# 25_USB2_USB3_TypeC_Port.net
KiCad netlist of a schematic drawn in Altium Designer
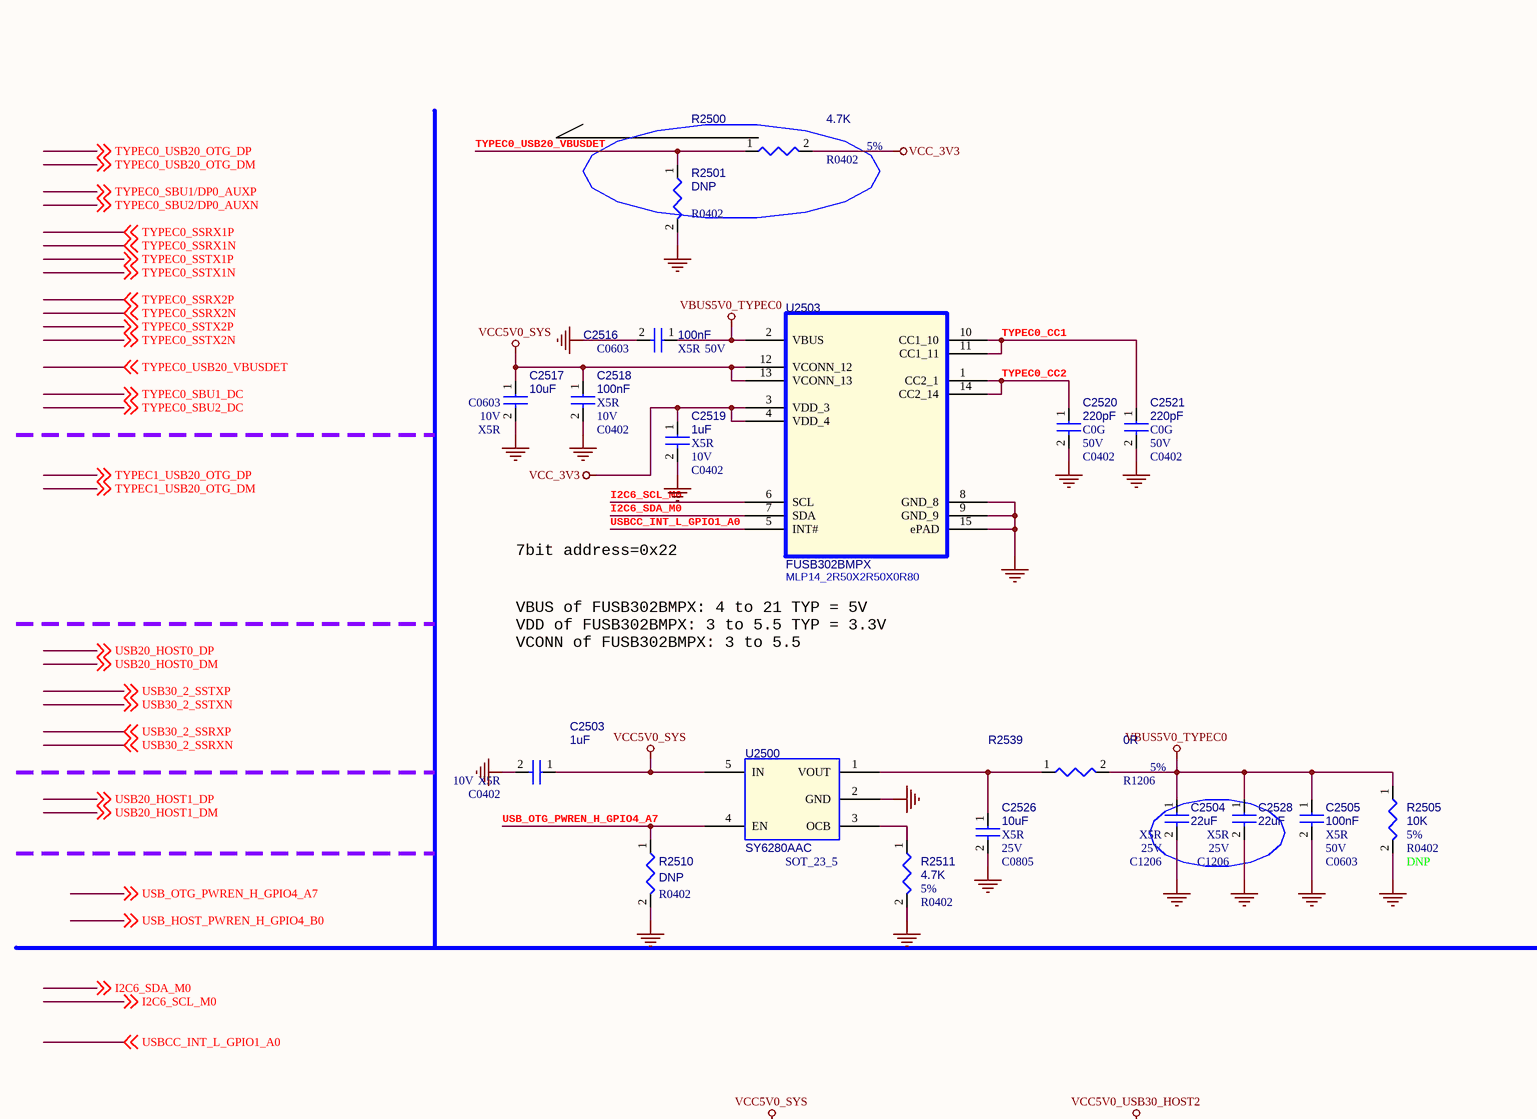
[diagram p0: 25.USB2_USB3_TypeC Port.SchDoc, top left]
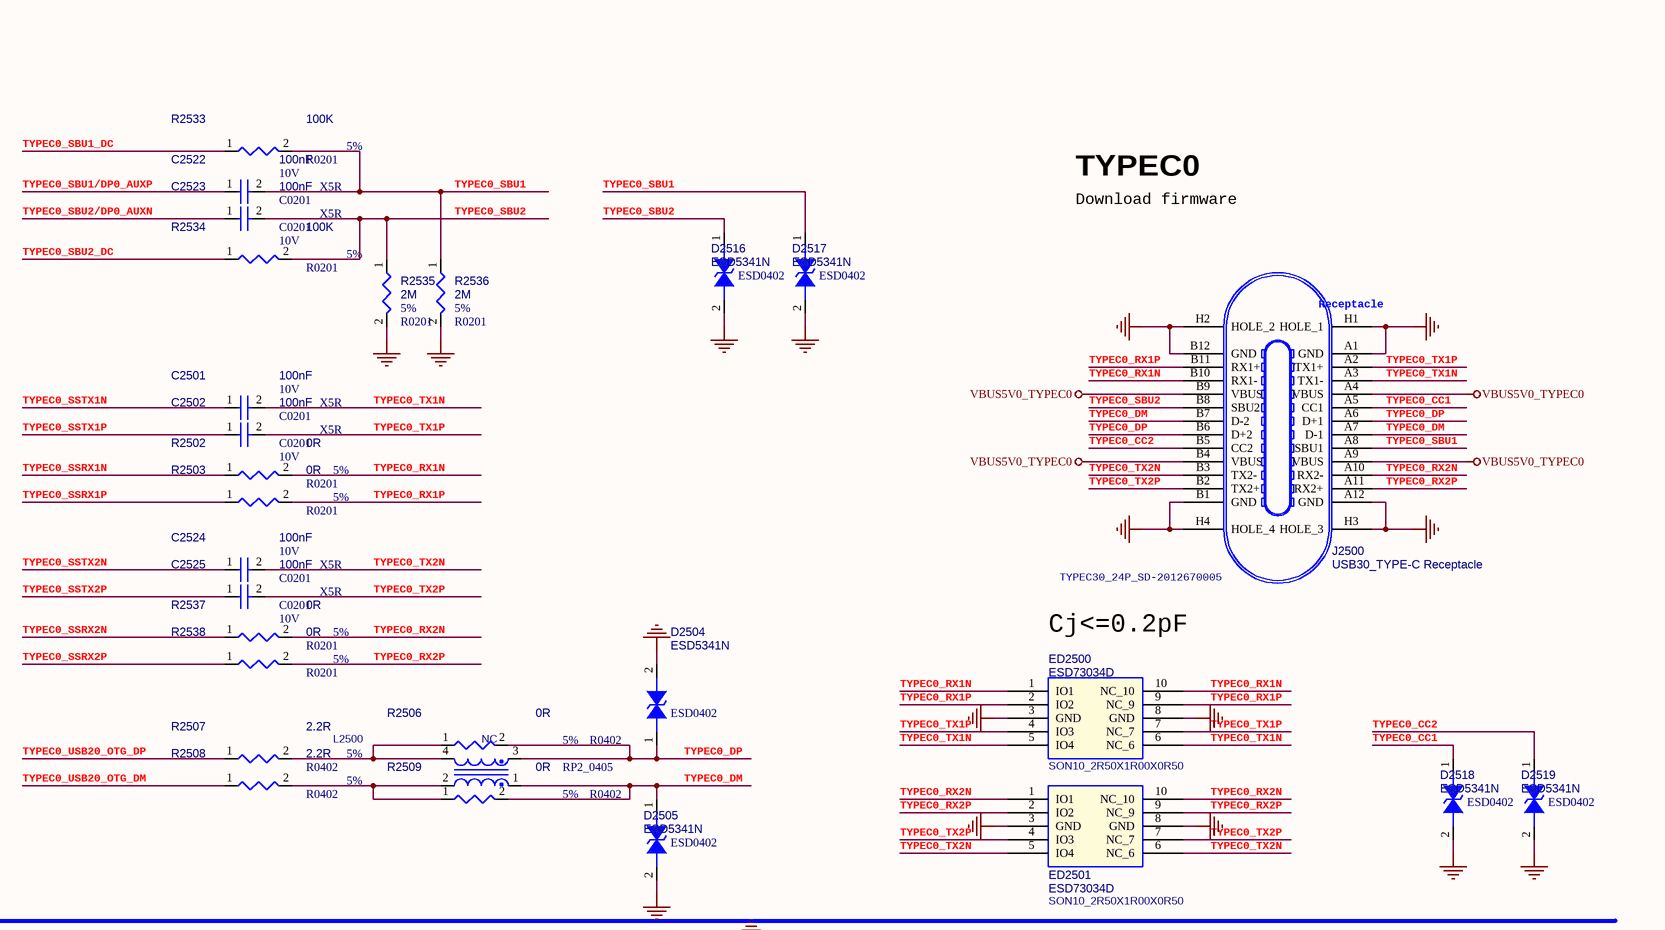
[diagram p1: 25.USB2_USB3_TypeC Port.SchDoc, top right]
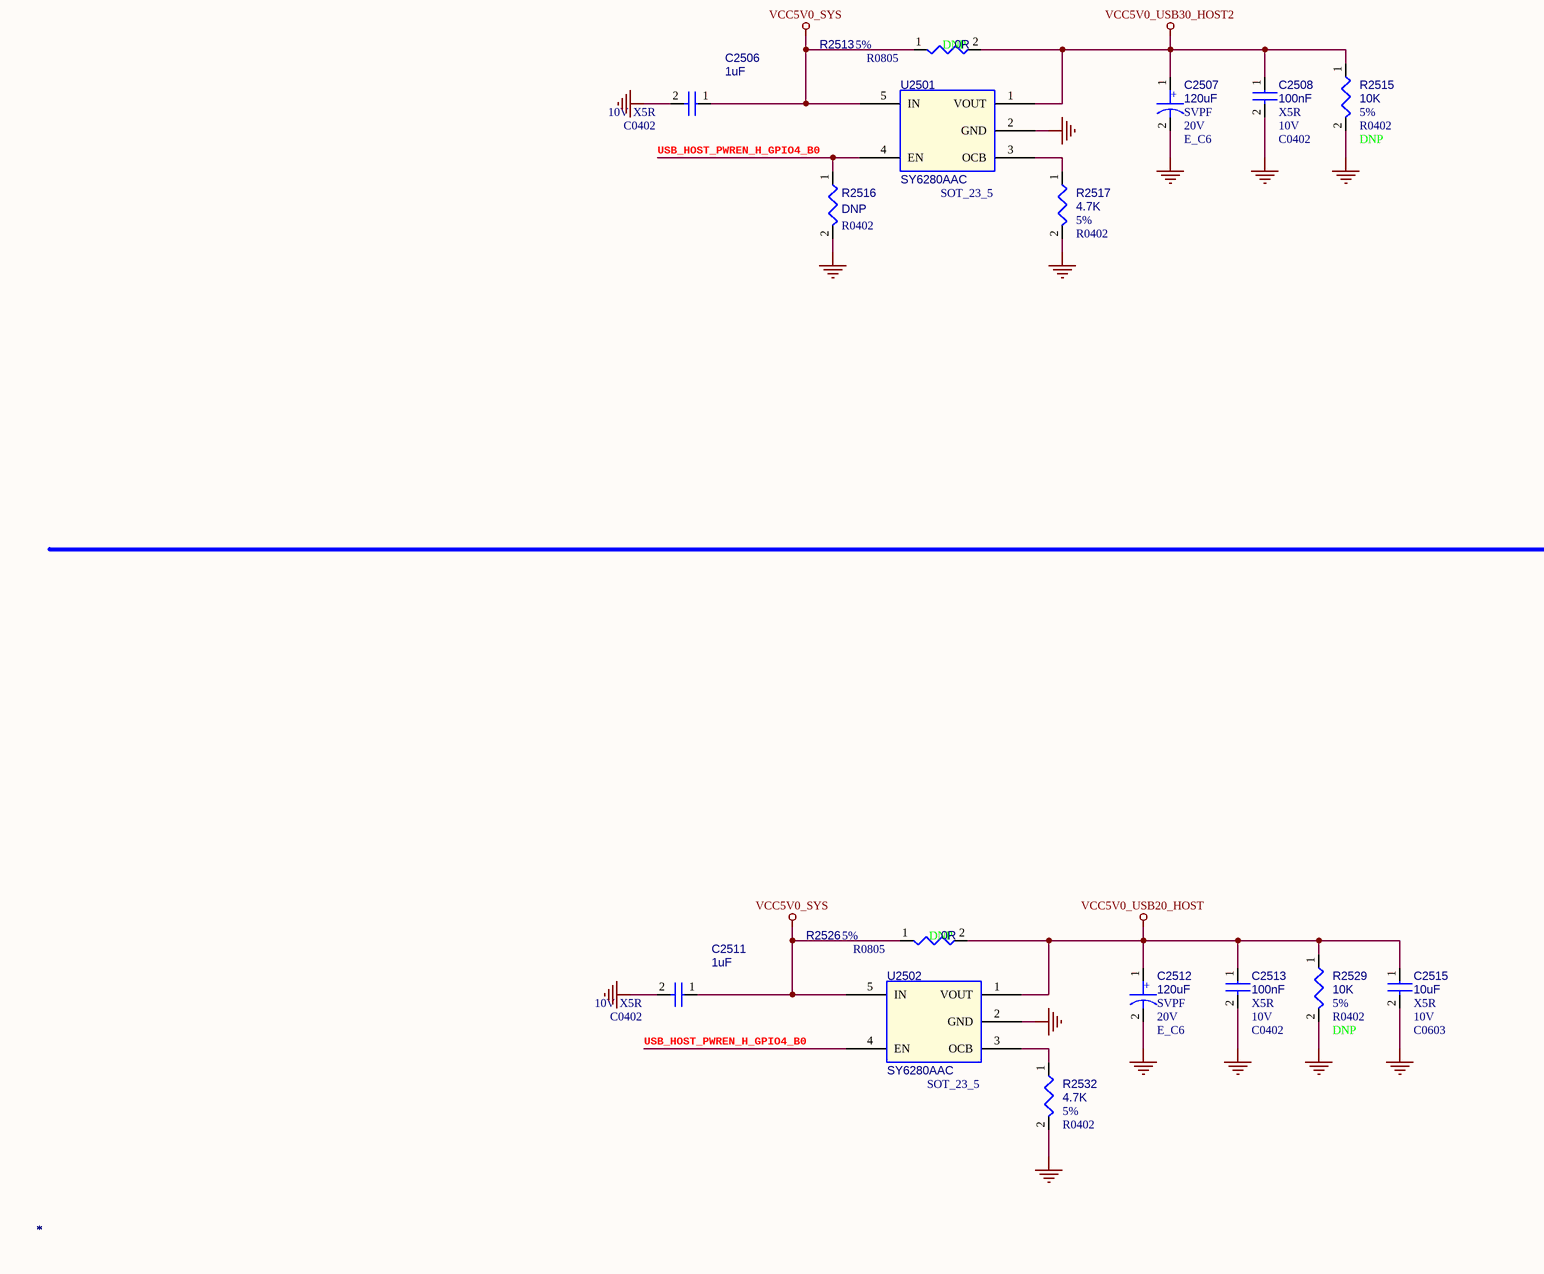
[diagram p2: 25.USB2_USB3_TypeC Port.SchDoc, bottom left]
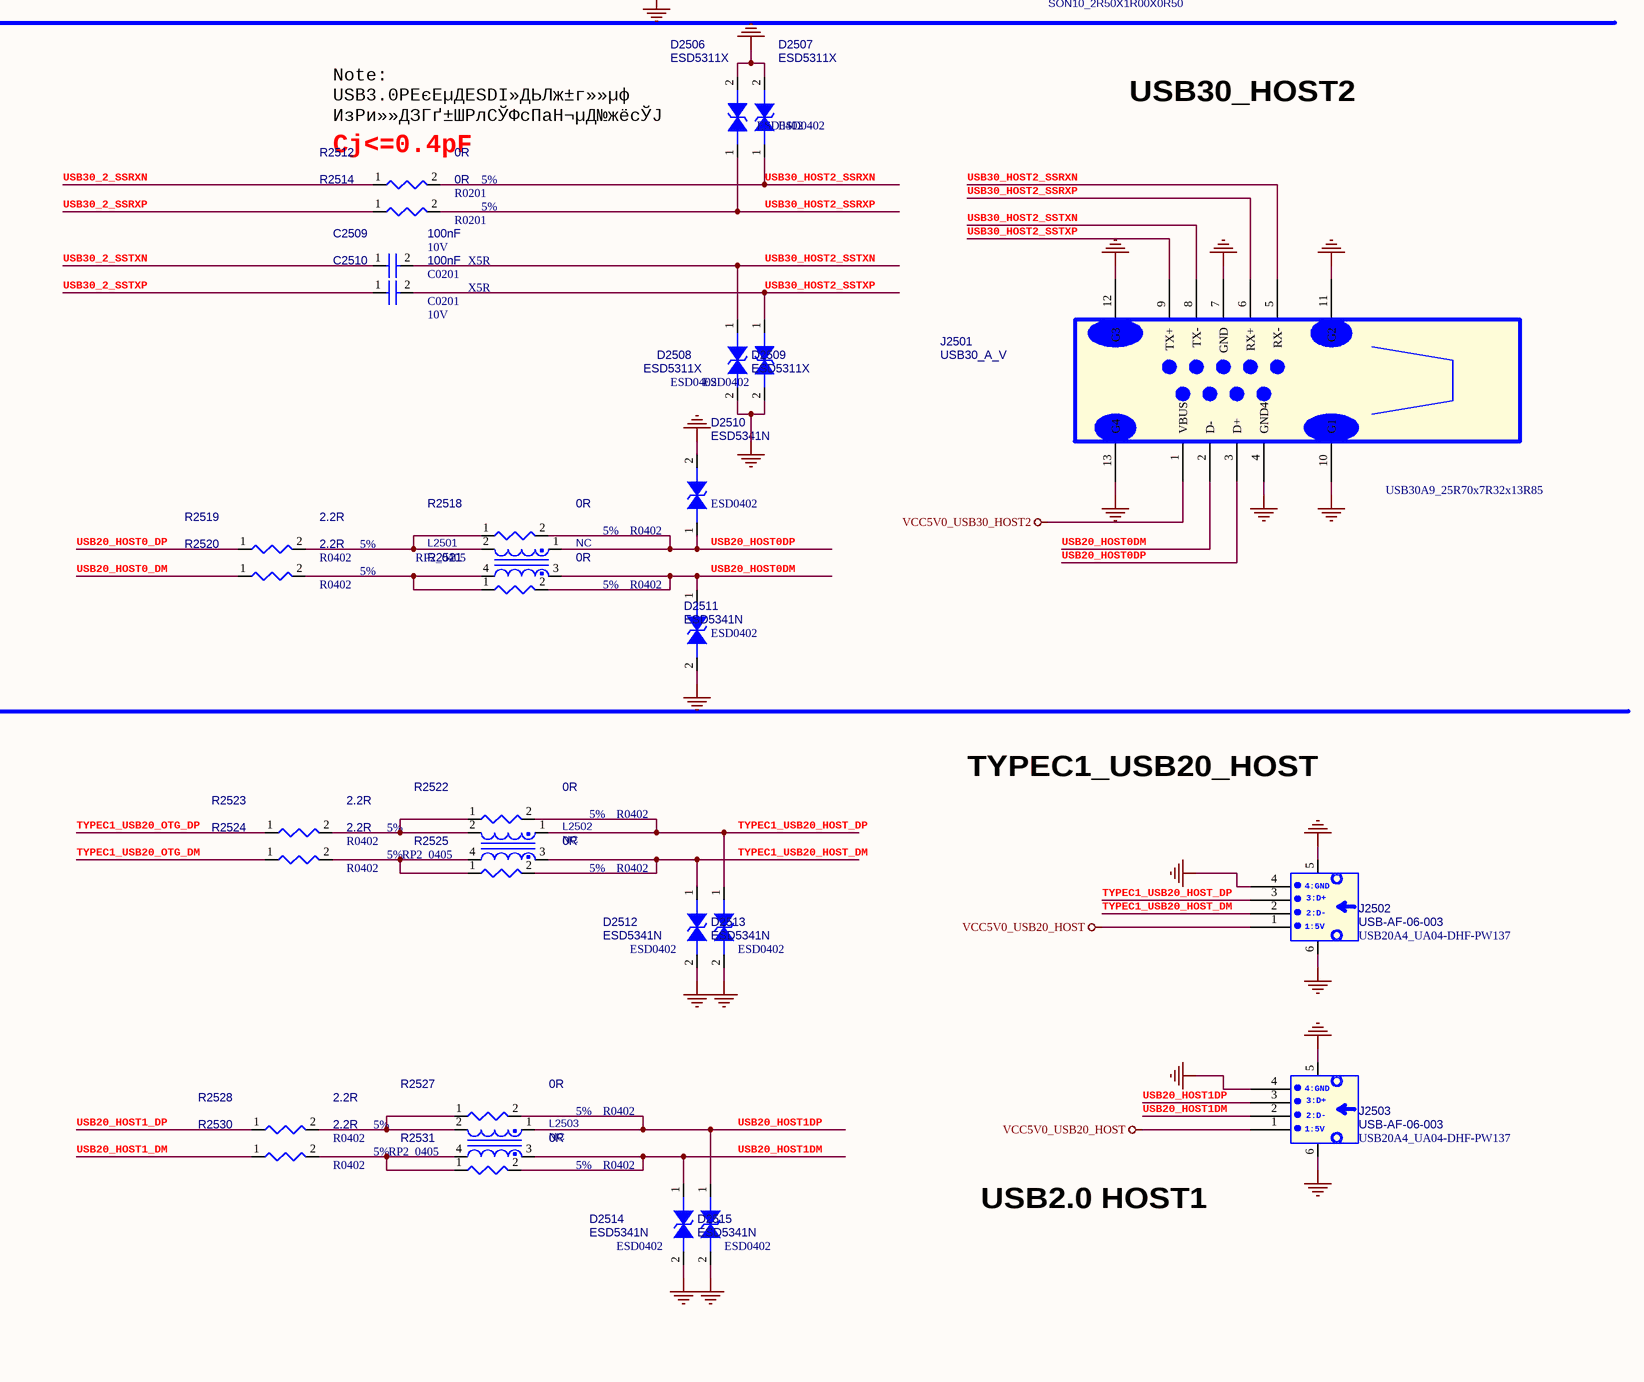
[diagram p3: 25.USB2_USB3_TypeC Port.SchDoc, bottom right]

(export (version "E")
  (design (tool "Eeschema 10.0.6"))
  (components
    (comp (ref "C2501")
      (value "*")
      (footprint "C0201")
      (description "cap,100.00nF,+/-10%,10V,X5R,C0201")
      (fields
        (field (name "VOLTAGE") "10V")
        (field (name "PCB FOOTPRINT") "C0201")
        (field (name "DIELECTRIC") "X5R")
        (field (name "MANUFACTURER") "TDK")
        (field (name "TOLERANCE") "10%")
        (field (name "ALTIUM_UNNAMED_1") "100nF")
        (field (name "CREATED BY") "JJJ")
      )
      (libsource (lib "*") (part "CAP NP"))
    )
    (comp (ref "C2502")
      (value "*")
      (footprint "C0201")
      (description "cap,100.00nF,+/-10%,10V,X5R,C0201")
      (fields
        (field (name "VOLTAGE") "10V")
        (field (name "PCB FOOTPRINT") "C0201")
        (field (name "DIELECTRIC") "X5R")
        (field (name "MANUFACTURER") "TDK")
        (field (name "TOLERANCE") "10%")
        (field (name "ALTIUM_UNNAMED_1") "100nF")
        (field (name "CREATED BY") "JJJ")
      )
      (libsource (lib "*") (part "CAP NP"))
    )
    (comp (ref "C2503")
      (value "*")
      (footprint "C0402")
      (description "cap,1.00uF,+/-10%,10V,X5R,C0402")
      (fields
        (field (name "VOLTAGE") "10V")
        (field (name "PCB FOOTPRINT") "C0402")
        (field (name "DIELECTRIC") "X5R")
        (field (name "MANUFACTURER") "TDK")
        (field (name "TOLERANCE") "10%")
        (field (name "ALTIUM_UNNAMED_1") "1uF")
        (field (name "CREATED BY") "JJJ")
      )
      (libsource (lib "*") (part "CAP NP"))
    )
    (comp (ref "C2504")
      (value "*")
      (footprint "C1206")
      (description "cap,22.00uF,+/-20%,25V,X5R,C1206")
      (fields
        (field (name "VOLTAGE") "25V")
        (field (name "PCB FOOTPRINT") "C1206")
        (field (name "DIELECTRIC") "X5R")
        (field (name "MANUFACTURER") "TDK")
        (field (name "TOLERANCE") "20%")
        (field (name "ALTIUM_UNNAMED_1") "22uF")
        (field (name "CREATED BY") "JJJ")
      )
      (libsource (lib "*") (part "CAP NP"))
    )
    (comp (ref "C2505")
      (value "*")
      (footprint "C0603")
      (description "cap,100.00nF,+/-10%,50V,X5R,C0603")
      (fields
        (field (name "VOLTAGE") "50V")
        (field (name "PCB FOOTPRINT") "C0603")
        (field (name "DIELECTRIC") "X5R")
        (field (name "TOLERANCE") "10%")
        (field (name "MANUFACTURER") "TDK")
        (field (name "ALTIUM_UNNAMED_1") "100nF")
        (field (name "CREATED BY") "JJJ")
      )
      (libsource (lib "*") (part "CAP NP"))
    )
    (comp (ref "C2506")
      (value "*")
      (footprint "C0402")
      (description "cap,1.00uF,+/-10%,10V,X5R,C0402")
      (fields
        (field (name "VOLTAGE") "10V")
        (field (name "PCB FOOTPRINT") "C0402")
        (field (name "DIELECTRIC") "X5R")
        (field (name "MANUFACTURER") "TDK")
        (field (name "TOLERANCE") "10%")
        (field (name "ALTIUM_UNNAMED_1") "1uF")
        (field (name "CREATED BY") "JJJ")
      )
      (libsource (lib "*") (part "CAP NP"))
    )
    (comp (ref "C2507")
      (value "*")
      (footprint "E_C6")
      (description "120uF,20V,25mR,SVPF")
      (fields
        (field (name "VOLTAGE") "20V")
        (field (name "DIELECTRIC") "SVPF")
        (field (name "PCB FOOTPRINT") "E_C6")
        (field (name "TOLERANCE") "20%")
        (field (name "MANUFACTURER") "Panasonic")
        (field (name "ALTIUM_UNNAMED_1") "120uF")
        (field (name "CREATED BY") "YWQ")
      )
      (libsource (lib "*") (part "CAP"))
    )
    (comp (ref "C2508")
      (value "*")
      (footprint "C0402")
      (description "cap,100.00nF,+/-10%,10V,X5R,C0402")
      (fields
        (field (name "VOLTAGE") "10V")
        (field (name "PCB FOOTPRINT") "C0402")
        (field (name "DIELECTRIC") "X5R")
        (field (name "MANUFACTURER") "TDK")
        (field (name "TOLERANCE") "10%")
        (field (name "ALTIUM_UNNAMED_1") "100nF")
        (field (name "CREATED BY") "JJJ")
      )
      (libsource (lib "*") (part "CAP NP"))
    )
    (comp (ref "C2509")
      (value "*")
      (footprint "C0201")
      (description "cap,100.00nF,+/-10%,10V,X5R,C0201")
      (fields
        (field (name "VOLTAGE") "10V")
        (field (name "PCB FOOTPRINT") "C0201")
        (field (name "DIELECTRIC") "X5R")
        (field (name "MANUFACTURER") "TDK")
        (field (name "TOLERANCE") "10%")
        (field (name "ALTIUM_UNNAMED_1") "100nF")
        (field (name "CREATED BY") "JJJ")
      )
      (libsource (lib "*") (part "CAP NP"))
    )
    (comp (ref "C2510")
      (value "*")
      (footprint "C0201")
      (description "cap,100.00nF,+/-10%,10V,X5R,C0201")
      (fields
        (field (name "VOLTAGE") "10V")
        (field (name "PCB FOOTPRINT") "C0201")
        (field (name "DIELECTRIC") "X5R")
        (field (name "MANUFACTURER") "TDK")
        (field (name "TOLERANCE") "10%")
        (field (name "ALTIUM_UNNAMED_1") "100nF")
        (field (name "CREATED BY") "JJJ")
      )
      (libsource (lib "*") (part "CAP NP"))
    )
    (comp (ref "C2511")
      (value "*")
      (footprint "C0402")
      (description "cap,1.00uF,+/-10%,10V,X5R,C0402")
      (fields
        (field (name "VOLTAGE") "10V")
        (field (name "PCB FOOTPRINT") "C0402")
        (field (name "DIELECTRIC") "X5R")
        (field (name "MANUFACTURER") "TDK")
        (field (name "TOLERANCE") "10%")
        (field (name "ALTIUM_UNNAMED_1") "1uF")
        (field (name "CREATED BY") "JJJ")
      )
      (libsource (lib "*") (part "CAP NP"))
    )
    (comp (ref "C2512")
      (value "*")
      (footprint "E_C6")
      (description "120uF,20V,25mR,SVPF")
      (fields
        (field (name "VOLTAGE") "20V")
        (field (name "DIELECTRIC") "SVPF")
        (field (name "PCB FOOTPRINT") "E_C6")
        (field (name "MANUFACTURER") "Panasonic")
        (field (name "TOLERANCE") "20%")
        (field (name "ALTIUM_UNNAMED_1") "120uF")
        (field (name "CREATED BY") "YWQ")
      )
      (libsource (lib "*") (part "CAP"))
    )
    (comp (ref "C2513")
      (value "*")
      (footprint "C0402")
      (description "cap,100.00nF,+/-10%,10V,X5R,C0402")
      (fields
        (field (name "VOLTAGE") "10V")
        (field (name "PCB FOOTPRINT") "C0402")
        (field (name "DIELECTRIC") "X5R")
        (field (name "TOLERANCE") "10%")
        (field (name "MANUFACTURER") "TDK")
        (field (name "ALTIUM_UNNAMED_1") "100nF")
        (field (name "CREATED BY") "JJJ")
      )
      (libsource (lib "*") (part "CAP NP"))
    )
    (comp (ref "C2515")
      (value "*")
      (footprint "C0603")
      (description "cap,10.00uF,+/-10%,10V,X5R,C0603")
      (fields
        (field (name "VOLTAGE") "10V")
        (field (name "PCB FOOTPRINT") "C0603")
        (field (name "DIELECTRIC") "X5R")
        (field (name "MANUFACTURER") "TDK")
        (field (name "TOLERANCE") "10%")
        (field (name "ALTIUM_UNNAMED_1") "10uF")
        (field (name "CREATED BY") "JJJ")
      )
      (libsource (lib "*") (part "CAP NP"))
    )
    (comp (ref "C2516")
      (value "*")
      (footprint "C0603")
      (description "cap,100.00nF,+/-10%,50V,X5R,C0603")
      (fields
        (field (name "VOLTAGE") "50V")
        (field (name "PCB FOOTPRINT") "C0603")
        (field (name "DIELECTRIC") "X5R")
        (field (name "MANUFACTURER") "TDK")
        (field (name "TOLERANCE") "10%")
        (field (name "ALTIUM_UNNAMED_1") "100nF")
        (field (name "CREATED BY") "JJJ")
      )
      (libsource (lib "*") (part "CAP NP"))
    )
    (comp (ref "C2517")
      (value "*")
      (footprint "C0603")
      (description "cap,10.00uF,+/-10%,10V,X5R,C0603")
      (fields
        (field (name "VOLTAGE") "10V")
        (field (name "PCB FOOTPRINT") "C0603")
        (field (name "DIELECTRIC") "X5R")
        (field (name "TOLERANCE") "10%")
        (field (name "MANUFACTURER") "TDK")
        (field (name "ALTIUM_UNNAMED_1") "10uF")
        (field (name "CREATED BY") "JJJ")
      )
      (libsource (lib "*") (part "CAP NP"))
    )
    (comp (ref "C2518")
      (value "*")
      (footprint "C0402")
      (description "cap,100.00nF,+/-10%,10V,X5R,C0402")
      (fields
        (field (name "VOLTAGE") "10V")
        (field (name "PCB FOOTPRINT") "C0402")
        (field (name "DIELECTRIC") "X5R")
        (field (name "MANUFACTURER") "TDK")
        (field (name "TOLERANCE") "10%")
        (field (name "ALTIUM_UNNAMED_1") "100nF")
        (field (name "CREATED BY") "JJJ")
      )
      (libsource (lib "*") (part "CAP NP"))
    )
    (comp (ref "C2519")
      (value "*")
      (footprint "C0402")
      (description "cap,1.00uF,+/-10%,10V,X5R,C0402")
      (fields
        (field (name "VOLTAGE") "10V")
        (field (name "PCB FOOTPRINT") "C0402")
        (field (name "DIELECTRIC") "X5R")
        (field (name "MANUFACTURER") "TDK")
        (field (name "TOLERANCE") "10%")
        (field (name "ALTIUM_UNNAMED_1") "1uF")
        (field (name "CREATED BY") "JJJ")
      )
      (libsource (lib "*") (part "CAP NP"))
    )
    (comp (ref "C2520")
      (value "*")
      (footprint "C0402")
      (description "cap,220.00pF,+/-10%,50V,C0G,C0402")
      (fields
        (field (name "VOLTAGE") "50V")
        (field (name "PCB FOOTPRINT") "C0402")
        (field (name "DIELECTRIC") "C0G")
        (field (name "TOLERANCE") "10%")
        (field (name "MANUFACTURER") "TDK")
        (field (name "ALTIUM_UNNAMED_1") "220pF")
        (field (name "CREATED BY") "JJJ")
      )
      (libsource (lib "*") (part "CAP NP"))
    )
    (comp (ref "C2521")
      (value "*")
      (footprint "C0402")
      (description "cap,220.00pF,+/-10%,50V,C0G,C0402")
      (fields
        (field (name "VOLTAGE") "50V")
        (field (name "PCB FOOTPRINT") "C0402")
        (field (name "DIELECTRIC") "C0G")
        (field (name "TOLERANCE") "10%")
        (field (name "MANUFACTURER") "TDK")
        (field (name "ALTIUM_UNNAMED_1") "220pF")
        (field (name "CREATED BY") "JJJ")
      )
      (libsource (lib "*") (part "CAP NP"))
    )
    (comp (ref "C2522")
      (value "*")
      (footprint "C0201")
      (description "cap,100.00nF,+/-10%,10V,X5R,C0201")
      (fields
        (field (name "VOLTAGE") "10V")
        (field (name "PCB FOOTPRINT") "C0201")
        (field (name "DIELECTRIC") "X5R")
        (field (name "TOLERANCE") "10%")
        (field (name "MANUFACTURER") "TDK")
        (field (name "ALTIUM_UNNAMED_1") "100nF")
        (field (name "CREATED BY") "JJJ")
      )
      (libsource (lib "*") (part "CAP NP"))
    )
    (comp (ref "C2523")
      (value "*")
      (footprint "C0201")
      (description "cap,100.00nF,+/-10%,10V,X5R,C0201")
      (fields
        (field (name "VOLTAGE") "10V")
        (field (name "PCB FOOTPRINT") "C0201")
        (field (name "DIELECTRIC") "X5R")
        (field (name "TOLERANCE") "10%")
        (field (name "MANUFACTURER") "TDK")
        (field (name "ALTIUM_UNNAMED_1") "100nF")
        (field (name "CREATED BY") "JJJ")
      )
      (libsource (lib "*") (part "CAP NP"))
    )
    (comp (ref "C2524")
      (value "*")
      (footprint "C0201")
      (description "cap,100.00nF,+/-10%,10V,X5R,C0201")
      (fields
        (field (name "VOLTAGE") "10V")
        (field (name "PCB FOOTPRINT") "C0201")
        (field (name "DIELECTRIC") "X5R")
        (field (name "MANUFACTURER") "TDK")
        (field (name "TOLERANCE") "10%")
        (field (name "ALTIUM_UNNAMED_1") "100nF")
        (field (name "CREATED BY") "JJJ")
      )
      (libsource (lib "*") (part "CAP NP"))
    )
    (comp (ref "C2525")
      (value "*")
      (footprint "C0201")
      (description "cap,100.00nF,+/-10%,10V,X5R,C0201")
      (fields
        (field (name "VOLTAGE") "10V")
        (field (name "PCB FOOTPRINT") "C0201")
        (field (name "DIELECTRIC") "X5R")
        (field (name "MANUFACTURER") "TDK")
        (field (name "TOLERANCE") "10%")
        (field (name "ALTIUM_UNNAMED_1") "100nF")
        (field (name "CREATED BY") "JJJ")
      )
      (libsource (lib "*") (part "CAP NP"))
    )
    (comp (ref "C2526")
      (value "*")
      (footprint "C0805")
      (description "cap,10.00uF,+/-10%,25V,X5R,C0805")
      (fields
        (field (name "VOLTAGE") "25V")
        (field (name "PCB FOOTPRINT") "C0805")
        (field (name "DIELECTRIC") "X5R")
        (field (name "MANUFACTURER") "TDK")
        (field (name "TOLERANCE") "10%")
        (field (name "ALTIUM_UNNAMED_1") "10uF")
        (field (name "CREATED BY") "JJJ")
      )
      (libsource (lib "*") (part "CAP NP"))
    )
    (comp (ref "C2528")
      (value "*")
      (footprint "C1206")
      (description "cap,22.00uF,+/-20%,25V,X5R,C1206")
      (fields
        (field (name "VOLTAGE") "25V")
        (field (name "PCB FOOTPRINT") "C1206")
        (field (name "DIELECTRIC") "X5R")
        (field (name "TOLERANCE") "20%")
        (field (name "MANUFACTURER") "TDK")
        (field (name "ALTIUM_UNNAMED_1") "22uF")
        (field (name "CREATED BY") "JJJ")
      )
      (libsource (lib "*") (part "CAP NP"))
    )
    (comp (ref "D2504")
      (value "*")
      (footprint "ESD0402")
      (description "1-Line, Bi-directional, Transient Voltage Suppressors.1pF.")
      (fields
        (field (name "PCB FOOTPRINT") "ESD0402")
        (field (name "MANUFACTURER") "WillSemi(О¤¶ы°лµјМе)")
        (field (name "ALTIUM_UNNAMED_1") "ESD5341N")
        (field (name "CREATED BY") "JJJ")
      )
      (libsource (lib "*") (part "DIODE BI_DIR TRIG"))
    )
    (comp (ref "D2505")
      (value "*")
      (footprint "ESD0402")
      (description "1-Line, Bi-directional, Transient Voltage Suppressors.1pF.")
      (fields
        (field (name "PCB FOOTPRINT") "ESD0402")
        (field (name "MANUFACTURER") "WillSemi(О¤¶ы°лµјМе)")
        (field (name "ALTIUM_UNNAMED_1") "ESD5341N")
        (field (name "CREATED BY") "JJJ")
      )
      (libsource (lib "*") (part "DIODE BI_DIR TRIG"))
    )
    (comp (ref "D2506")
      (value "*")
      (footprint "ESD0402")
      (description "1-Line, Bi-directional, Transient Voltage Suppressors.0.25pF.")
      (fields
        (field (name "PCB FOOTPRINT") "ESD0402")
        (field (name "MANUFACTURER") "WillSemi(О¤¶ы°лµјМе)")
        (field (name "ALTIUM_UNNAMED_1") "ESD5311X")
        (field (name "CREATED BY") "JJJ")
      )
      (libsource (lib "*") (part "DIODE BI_DIR TRIG"))
    )
    (comp (ref "D2507")
      (value "*")
      (footprint "ESD0402")
      (description "1-Line, Bi-directional, Transient Voltage Suppressors.0.25pF.")
      (fields
        (field (name "PCB FOOTPRINT") "ESD0402")
        (field (name "MANUFACTURER") "WillSemi(О¤¶ы°лµјМе)")
        (field (name "ALTIUM_UNNAMED_1") "ESD5311X")
        (field (name "CREATED BY") "JJJ")
      )
      (libsource (lib "*") (part "DIODE BI_DIR TRIG"))
    )
    (comp (ref "D2508")
      (value "*")
      (footprint "ESD0402")
      (description "1-Line, Bi-directional, Transient Voltage Suppressors.0.25pF.")
      (fields
        (field (name "PCB FOOTPRINT") "ESD0402")
        (field (name "MANUFACTURER") "WillSemi(О¤¶ы°лµјМе)")
        (field (name "ALTIUM_UNNAMED_1") "ESD5311X")
        (field (name "CREATED BY") "JJJ")
      )
      (libsource (lib "*") (part "DIODE BI_DIR TRIG"))
    )
    (comp (ref "D2509")
      (value "*")
      (footprint "ESD0402")
      (description "1-Line, Bi-directional, Transient Voltage Suppressors.0.25pF.")
      (fields
        (field (name "PCB FOOTPRINT") "ESD0402")
        (field (name "MANUFACTURER") "WillSemi(О¤¶ы°лµјМе)")
        (field (name "ALTIUM_UNNAMED_1") "ESD5311X")
        (field (name "CREATED BY") "JJJ")
      )
      (libsource (lib "*") (part "DIODE BI_DIR TRIG"))
    )
    (comp (ref "D2510")
      (value "*")
      (footprint "ESD0402")
      (description "1-Line, Bi-directional, Transient Voltage Suppressors.1pF.")
      (fields
        (field (name "PCB FOOTPRINT") "ESD0402")
        (field (name "MANUFACTURER") "WillSemi(О¤¶ы°лµјМе)")
        (field (name "ALTIUM_UNNAMED_1") "ESD5341N")
        (field (name "CREATED BY") "JJJ")
      )
      (libsource (lib "*") (part "DIODE BI_DIR TRIG"))
    )
    (comp (ref "D2511")
      (value "*")
      (footprint "ESD0402")
      (description "1-Line, Bi-directional, Transient Voltage Suppressors.1pF.")
      (fields
        (field (name "PCB FOOTPRINT") "ESD0402")
        (field (name "MANUFACTURER") "WillSemi(О¤¶ы°лµјМе)")
        (field (name "ALTIUM_UNNAMED_1") "ESD5341N")
        (field (name "CREATED BY") "JJJ")
      )
      (libsource (lib "*") (part "DIODE BI_DIR TRIG"))
    )
    (comp (ref "D2512")
      (value "*")
      (footprint "ESD0402")
      (description "1-Line, Bi-directional, Transient Voltage Suppressors.1pF.")
      (fields
        (field (name "PCB FOOTPRINT") "ESD0402")
        (field (name "MANUFACTURER") "WillSemi(О¤¶ы°лµјМе)")
        (field (name "ALTIUM_UNNAMED_1") "ESD5341N")
        (field (name "CREATED BY") "JJJ")
      )
      (libsource (lib "*") (part "DIODE BI_DIR TRIG"))
    )
    (comp (ref "D2513")
      (value "*")
      (footprint "ESD0402")
      (description "1-Line, Bi-directional, Transient Voltage Suppressors.1pF.")
      (fields
        (field (name "PCB FOOTPRINT") "ESD0402")
        (field (name "MANUFACTURER") "WillSemi(О¤¶ы°лµјМе)")
        (field (name "ALTIUM_UNNAMED_1") "ESD5341N")
        (field (name "CREATED BY") "JJJ")
      )
      (libsource (lib "*") (part "DIODE BI_DIR TRIG"))
    )
    (comp (ref "D2514")
      (value "*")
      (footprint "ESD0402")
      (description "1-Line, Bi-directional, Transient Voltage Suppressors.1pF.")
      (fields
        (field (name "PCB FOOTPRINT") "ESD0402")
        (field (name "MANUFACTURER") "WillSemi(О¤¶ы°лµјМе)")
        (field (name "ALTIUM_UNNAMED_1") "ESD5341N")
        (field (name "CREATED BY") "JJJ")
      )
      (libsource (lib "*") (part "DIODE BI_DIR TRIG"))
    )
    (comp (ref "D2515")
      (value "*")
      (footprint "ESD0402")
      (description "1-Line, Bi-directional, Transient Voltage Suppressors.1pF.")
      (fields
        (field (name "PCB FOOTPRINT") "ESD0402")
        (field (name "MANUFACTURER") "WillSemi(О¤¶ы°лµјМе)")
        (field (name "ALTIUM_UNNAMED_1") "ESD5341N")
        (field (name "CREATED BY") "JJJ")
      )
      (libsource (lib "*") (part "DIODE BI_DIR TRIG"))
    )
    (comp (ref "D2516")
      (value "*")
      (footprint "ESD0402")
      (description "1-Line, Bi-directional, Transient Voltage Suppressors.1pF.")
      (fields
        (field (name "PCB FOOTPRINT") "ESD0402")
        (field (name "MANUFACTURER") "WillSemi(О¤¶ы°лµјМе)")
        (field (name "ALTIUM_UNNAMED_1") "ESD5341N")
        (field (name "CREATED BY") "JJJ")
      )
      (libsource (lib "*") (part "DIODE BI_DIR TRIG"))
    )
    (comp (ref "D2517")
      (value "*")
      (footprint "ESD0402")
      (description "1-Line, Bi-directional, Transient Voltage Suppressors.1pF.")
      (fields
        (field (name "PCB FOOTPRINT") "ESD0402")
        (field (name "MANUFACTURER") "WillSemi(О¤¶ы°лµјМе)")
        (field (name "ALTIUM_UNNAMED_1") "ESD5341N")
        (field (name "CREATED BY") "JJJ")
      )
      (libsource (lib "*") (part "DIODE BI_DIR TRIG"))
    )
    (comp (ref "D2518")
      (value "*")
      (footprint "ESD0402")
      (description "1-Line, Bi-directional, Transient Voltage Suppressors.1pF.")
      (fields
        (field (name "PCB FOOTPRINT") "ESD0402")
        (field (name "MANUFACTURER") "WillSemi(О¤¶ы°лµјМе)")
        (field (name "ALTIUM_UNNAMED_1") "ESD5341N")
        (field (name "CREATED BY") "JJJ")
      )
      (libsource (lib "*") (part "DIODE BI_DIR TRIG"))
    )
    (comp (ref "D2519")
      (value "*")
      (footprint "ESD0402")
      (description "1-Line, Bi-directional, Transient Voltage Suppressors.1pF.")
      (fields
        (field (name "PCB FOOTPRINT") "ESD0402")
        (field (name "MANUFACTURER") "WillSemi(О¤¶ы°лµјМе)")
        (field (name "ALTIUM_UNNAMED_1") "ESD5341N")
        (field (name "CREATED BY") "JJJ")
      )
      (libsource (lib "*") (part "DIODE BI_DIR TRIG"))
    )
    (comp (ref "ED2500")
      (value "*")
      (footprint "SON10_2R50X1R00X0R50")
      (description "4-Lines, Uni-directional, Ultra-low Capacitance Transient Voltage Suppressors")
      (fields
        (field (name "PCB FOOTPRINT") "SON10_2R50X1R00X0R50")
        (field (name "MANUFACTURER") "WillSemi(О¤¶ы°лµјМе)")
        (field (name "ALTIUM_UNNAMED_1") "ESD73034D")
        (field (name "CREATED BY") "JJJ")
      )
      (libsource (lib "*") (part "ESD_ESD5304D"))
    )
    (comp (ref "ED2501")
      (value "*")
      (footprint "SON10_2R50X1R00X0R50")
      (description "4-Lines, Uni-directional, Ultra-low Capacitance Transient Voltage Suppressors")
      (fields
        (field (name "PCB FOOTPRINT") "SON10_2R50X1R00X0R50")
        (field (name "MANUFACTURER") "WillSemi(О¤¶ы°лµјМе)")
        (field (name "ALTIUM_UNNAMED_1") "ESD73034D")
        (field (name "CREATED BY") "JJJ")
      )
      (libsource (lib "*") (part "ESD_ESD5304D"))
    )
    (comp (ref "J2500")
      (value "*")
      (footprint "TYPEC30_24P_SD-2012670005")
      (description "USB Type-CОФКЅДёЧщЈ¬Мщєё")
      (fields
        (field (name "PCB FOOTPRINT") "TYPEC30_24P_SD-2012670005")
        (field (name "MANUFACTURER PART NUMBER") "USB_TYPE-C-31-M-05")
        (field (name "MANUFACTURER") "є«ИЩ")
        (field (name "ALTIUM_UNNAMED_1") "USB30_TYPE-C Receptacle")
        (field (name "CREATED BY") "YWQ")
      )
      (libsource (lib "*") (part "USB30_TYPE-C Receptacle_0"))
    )
    (comp (ref "J2501")
      (value "*")
      (footprint "USB30")
      (description "USB3.0 AРНЈ¬ІаІеЈ¬ДёЧщЈ¬Іеєё")
      (fields
        (field (name "PCB FOOTPRINT") "USB30A9_25R70x7R32x13R85")
        (field (name "MANUFACTURER") "мч»ЄµзЧУ")
        (field (name "MANUFACTURER PART NUMBER") "UA09-SHF-PU03")
        (field (name "ALTIUM_UNNAMED_1") "USB30_A_V")
        (field (name "CREATED BY") "YWQ")
      )
      (libsource (lib "*") (part "USB30_TYPE_A_V_2"))
    )
    (comp (ref "J2502")
      (value "*")
      (footprint "USB20")
      (description "USB2.0 AРНБўКЅЦ±ІеНдЅЕДёЧщЈ¬Іеєё")
      (fields
        (field (name "PCB FOOTPRINT") "USB20A4_UA04-DHF-PW137")
        (field (name "MANUFACTURER") "НъїЖґп")
        (field (name "MANUFACTURER PART NUMBER") "USB-AF-06-003")
        (field (name "ALTIUM_UNNAMED_1") "USB-AF-06-003")
        (field (name "CREATED BY") "YWQ")
      )
      (libsource (lib "*") (part "USB20_TYPE_A"))
    )
    (comp (ref "J2503")
      (value "*")
      (footprint "USB20")
      (description "USB2.0 AРНБўКЅЦ±ІеНдЅЕДёЧщЈ¬Іеєё")
      (fields
        (field (name "PCB FOOTPRINT") "USB20A4_UA04-DHF-PW137")
        (field (name "MANUFACTURER") "НъїЖґп")
        (field (name "MANUFACTURER PART NUMBER") "USB-AF-06-003")
        (field (name "ALTIUM_UNNAMED_1") "USB-AF-06-003")
        (field (name "CREATED BY") "YWQ")
      )
      (libsource (lib "*") (part "USB20_TYPE_A"))
    )
    (comp (ref "L2500")
      (value "*")
      (footprint "L0402D")
      (description "Winding Type Common Mode Choke Coil")
      (fields
        (field (name "PCB FOOTPRINT") "RP2_0405")
        (field (name "MANUFACTURER") "sunlord")
        (field (name "TOLERANCE") "25%")
        (field (name "ALTIUM_UNNAMED_1") "NC")
        (field (name "CREATED BY") "JJJ")
      )
      (libsource (lib "*") (part "INDUCTOR COM"))
    )
    (comp (ref "L2501")
      (value "*")
      (footprint "L0402D")
      (description "Winding Type Common Mode Choke Coil")
      (fields
        (field (name "PCB FOOTPRINT") "RP2_0405")
        (field (name "MANUFACTURER") "sunlord")
        (field (name "TOLERANCE") "25%")
        (field (name "ALTIUM_UNNAMED_1") "NC")
        (field (name "CREATED BY") "JJJ")
      )
      (libsource (lib "") (part "INDUCTOR COM_1"))
    )
    (comp (ref "L2502")
      (value "*")
      (footprint "L0402D")
      (description "Winding Type Common Mode Choke Coil")
      (fields
        (field (name "PCB FOOTPRINT") "RP2_0405")
        (field (name "TOLERANCE") "25%")
        (field (name "MANUFACTURER") "sunlord")
        (field (name "ALTIUM_UNNAMED_1") "NC")
        (field (name "CREATED BY") "JJJ")
      )
      (libsource (lib "") (part "INDUCTOR COM_1"))
    )
    (comp (ref "L2503")
      (value "*")
      (footprint "L0402D")
      (description "Winding Type Common Mode Choke Coil")
      (fields
        (field (name "PCB FOOTPRINT") "RP2_0405")
        (field (name "TOLERANCE") "25%")
        (field (name "MANUFACTURER") "sunlord")
        (field (name "ALTIUM_UNNAMED_1") "NC")
        (field (name "CREATED BY") "JJJ")
      )
      (libsource (lib "") (part "INDUCTOR COM_1"))
    )
    (comp (ref "R2500")
      (value "*")
      (footprint "R0402")
      (description "НЁУГєсД¤µзЧи,4K7,+/-5%,R0402,1/16W.")
      (fields
        (field (name "PCB FOOTPRINT") "R0402")
        (field (name "TOLERANCE") "5%")
        (field (name "MANUFACTURER") "YAGEO")
        (field (name "ALTIUM_UNNAMED_1") "4.7K")
        (field (name "CREATED BY") "YTL")
      )
      (libsource (lib "*") (part "RESISTOR_Dup1"))
    )
    (comp (ref "R2501")
      (value "*")
      (footprint "R0402")
      (description "Did Not Place.")
      (fields
        (field (name "PCB FOOTPRINT") "R0402")
        (field (name "ALTIUM_UNNAMED_1") "DNP")
        (field (name "CREATED BY") "JJJ")
      )
      (libsource (lib "*") (part "RESISTOR_Dup1"))
    )
    (comp (ref "R2502")
      (value "*")
      (footprint "R0402")
      (description "НЁУГєсД¤µзЧи,0R,+/-5%,R0201,1/20W.")
      (fields
        (field (name "PCB FOOTPRINT") "R0201")
        (field (name "TOLERANCE") "5%")
        (field (name "MANUFACTURER") "YAGEO")
        (field (name "ALTIUM_UNNAMED_1") "0R")
        (field (name "CREATED BY") "YTL")
      )
      (libsource (lib "*") (part "RESISTOR_Dup1"))
    )
    (comp (ref "R2503")
      (value "*")
      (footprint "R0402")
      (description "НЁУГєсД¤µзЧи,0R,+/-5%,R0201,1/20W.")
      (fields
        (field (name "PCB FOOTPRINT") "R0201")
        (field (name "TOLERANCE") "5%")
        (field (name "MANUFACTURER") "YAGEO")
        (field (name "ALTIUM_UNNAMED_1") "0R")
        (field (name "CREATED BY") "YTL")
      )
      (libsource (lib "*") (part "RESISTOR_Dup1"))
    )
    (comp (ref "R2505")
      (value "*")
      (footprint "R0402")
      (description "НЁУГєсД¤µзЧи,10K,+/-5%,R0402,1/16W.")
      (fields
        (field (name "PCB FOOTPRINT") "R0402")
        (field (name "TOLERANCE") "5%")
        (field (name "OPTION") "DNP")
        (field (name "MANUFACTURER") "YAGEO")
        (field (name "ALTIUM_UNNAMED_1") "10K")
        (field (name "CREATED BY") "YTL")
      )
      (libsource (lib "*") (part "RESISTOR_Dup1"))
    )
    (comp (ref "R2506")
      (value "*")
      (footprint "R0402")
      (description "НЁУГєсД¤µзЧи,0R,+/-5%,R0402,1/16W.")
      (fields
        (field (name "PCB FOOTPRINT") "R0402")
        (field (name "TOLERANCE") "5%")
        (field (name "MANUFACTURER") "YAGEO")
        (field (name "ALTIUM_UNNAMED_1") "0R")
        (field (name "CREATED BY") "YTL")
      )
      (libsource (lib "*") (part "RESISTOR_Dup1"))
    )
    (comp (ref "R2507")
      (value "*")
      (footprint "R0402")
      (description "НЁУГєсД¤µзЧи,2R2,+/-5%,R0402,1/16W.")
      (fields
        (field (name "PCB FOOTPRINT") "R0402")
        (field (name "TOLERANCE") "5%")
        (field (name "MANUFACTURER") "YAGEO")
        (field (name "ALTIUM_UNNAMED_1") "2.2R")
        (field (name "CREATED BY") "YTL")
      )
      (libsource (lib "*") (part "RESISTOR_Dup1"))
    )
    (comp (ref "R2508")
      (value "*")
      (footprint "R0402")
      (description "НЁУГєсД¤µзЧи,2R2,+/-5%,R0402,1/16W.")
      (fields
        (field (name "PCB FOOTPRINT") "R0402")
        (field (name "TOLERANCE") "5%")
        (field (name "MANUFACTURER") "YAGEO")
        (field (name "ALTIUM_UNNAMED_1") "2.2R")
        (field (name "CREATED BY") "YTL")
      )
      (libsource (lib "*") (part "RESISTOR_Dup1"))
    )
    (comp (ref "R2509")
      (value "*")
      (footprint "R0402")
      (description "НЁУГєсД¤µзЧи,0R,+/-5%,R0402,1/16W.")
      (fields
        (field (name "PCB FOOTPRINT") "R0402")
        (field (name "TOLERANCE") "5%")
        (field (name "MANUFACTURER") "YAGEO")
        (field (name "ALTIUM_UNNAMED_1") "0R")
        (field (name "CREATED BY") "YTL")
      )
      (libsource (lib "*") (part "RESISTOR_Dup1"))
    )
    (comp (ref "R2510")
      (value "*")
      (footprint "R0402")
      (description "Did Not Place.")
      (fields
        (field (name "PCB FOOTPRINT") "R0402")
        (field (name "TOLERANCE") "0%")
        (field (name "ALTIUM_UNNAMED_1") "DNP")
        (field (name "CREATED BY") "JJJ")
      )
      (libsource (lib "*") (part "RESISTOR_Dup1"))
    )
    (comp (ref "R2511")
      (value "*")
      (footprint "R0402")
      (description "НЁУГєсД¤µзЧи,4K7,+/-5%,R0402,1/16W.")
      (fields
        (field (name "PCB FOOTPRINT") "R0402")
        (field (name "TOLERANCE") "5%")
        (field (name "MANUFACTURER") "YAGEO")
        (field (name "ALTIUM_UNNAMED_1") "4.7K")
        (field (name "CREATED BY") "YTL")
      )
      (libsource (lib "*") (part "RESISTOR_Dup1"))
    )
    (comp (ref "R2512")
      (value "*")
      (footprint "R0402")
      (description "НЁУГєсД¤µзЧи,0R,+/-5%,R0201,1/20W.")
      (fields
        (field (name "PCB FOOTPRINT") "R0201")
        (field (name "TOLERANCE") "5%")
        (field (name "MANUFACTURER") "YAGEO")
        (field (name "ALTIUM_UNNAMED_1") "0R")
        (field (name "CREATED BY") "YTL")
      )
      (libsource (lib "*") (part "RESISTOR_Dup1"))
    )
    (comp (ref "R2513")
      (value "*")
      (footprint "R0402")
      (description "НЁУГєсД¤µзЧи,0R,+/-5%,R0805,1/8W.")
      (fields
        (field (name "PCB FOOTPRINT") "R0805")
        (field (name "TOLERANCE") "5%")
        (field (name "OPTION") "DNP")
        (field (name "MANUFACTURER") "YAGEO")
        (field (name "ALTIUM_UNNAMED_1") "0R")
        (field (name "CREATED BY") "YTL")
      )
      (libsource (lib "*") (part "RESISTOR_Dup1"))
    )
    (comp (ref "R2514")
      (value "*")
      (footprint "R0402")
      (description "НЁУГєсД¤µзЧи,0R,+/-5%,R0201,1/20W.")
      (fields
        (field (name "PCB FOOTPRINT") "R0201")
        (field (name "TOLERANCE") "5%")
        (field (name "MANUFACTURER") "YAGEO")
        (field (name "ALTIUM_UNNAMED_1") "0R")
        (field (name "CREATED BY") "YTL")
      )
      (libsource (lib "*") (part "RESISTOR_Dup1"))
    )
    (comp (ref "R2515")
      (value "*")
      (footprint "R0402")
      (description "НЁУГєсД¤µзЧи,10K,+/-5%,R0402,1/16W.")
      (fields
        (field (name "PCB FOOTPRINT") "R0402")
        (field (name "TOLERANCE") "5%")
        (field (name "OPTION") "DNP")
        (field (name "MANUFACTURER") "YAGEO")
        (field (name "ALTIUM_UNNAMED_1") "10K")
        (field (name "CREATED BY") "YTL")
      )
      (libsource (lib "*") (part "RESISTOR_Dup1"))
    )
    (comp (ref "R2516")
      (value "*")
      (footprint "R0402")
      (description "Did Not Place.")
      (fields
        (field (name "PCB FOOTPRINT") "R0402")
        (field (name "TOLERANCE") "0%")
        (field (name "ALTIUM_UNNAMED_1") "DNP")
        (field (name "CREATED BY") "JJJ")
      )
      (libsource (lib "*") (part "RESISTOR_Dup1"))
    )
    (comp (ref "R2517")
      (value "*")
      (footprint "R0402")
      (description "НЁУГєсД¤µзЧи,4K7,+/-5%,R0402,1/16W.")
      (fields
        (field (name "PCB FOOTPRINT") "R0402")
        (field (name "TOLERANCE") "5%")
        (field (name "MANUFACTURER") "YAGEO")
        (field (name "ALTIUM_UNNAMED_1") "4.7K")
        (field (name "CREATED BY") "YTL")
      )
      (libsource (lib "*") (part "RESISTOR_Dup1"))
    )
    (comp (ref "R2518")
      (value "*")
      (footprint "R0402")
      (description "НЁУГєсД¤µзЧи,0R,+/-5%,R0402,1/16W.")
      (fields
        (field (name "PCB FOOTPRINT") "R0402")
        (field (name "TOLERANCE") "5%")
        (field (name "MANUFACTURER") "YAGEO")
        (field (name "ALTIUM_UNNAMED_1") "0R")
        (field (name "CREATED BY") "YTL")
      )
      (libsource (lib "*") (part "RESISTOR_Dup1"))
    )
    (comp (ref "R2519")
      (value "*")
      (footprint "R0402")
      (description "НЁУГєсД¤µзЧи,2R2,+/-5%,R0402,1/16W.")
      (fields
        (field (name "PCB FOOTPRINT") "R0402")
        (field (name "TOLERANCE") "5%")
        (field (name "MANUFACTURER") "YAGEO")
        (field (name "ALTIUM_UNNAMED_1") "2.2R")
        (field (name "CREATED BY") "YTL")
      )
      (libsource (lib "*") (part "RESISTOR_Dup1"))
    )
    (comp (ref "R2520")
      (value "*")
      (footprint "R0402")
      (description "НЁУГєсД¤µзЧи,2R2,+/-5%,R0402,1/16W.")
      (fields
        (field (name "PCB FOOTPRINT") "R0402")
        (field (name "TOLERANCE") "5%")
        (field (name "MANUFACTURER") "YAGEO")
        (field (name "ALTIUM_UNNAMED_1") "2.2R")
        (field (name "CREATED BY") "YTL")
      )
      (libsource (lib "*") (part "RESISTOR_Dup1"))
    )
    (comp (ref "R2521")
      (value "*")
      (footprint "R0402")
      (description "НЁУГєсД¤µзЧи,0R,+/-5%,R0402,1/16W.")
      (fields
        (field (name "PCB FOOTPRINT") "R0402")
        (field (name "TOLERANCE") "5%")
        (field (name "MANUFACTURER") "YAGEO")
        (field (name "ALTIUM_UNNAMED_1") "0R")
        (field (name "CREATED BY") "YTL")
      )
      (libsource (lib "*") (part "RESISTOR_Dup1"))
    )
    (comp (ref "R2522")
      (value "*")
      (footprint "R0402")
      (description "НЁУГєсД¤µзЧи,0R,+/-5%,R0402,1/16W.")
      (fields
        (field (name "PCB FOOTPRINT") "R0402")
        (field (name "TOLERANCE") "5%")
        (field (name "MANUFACTURER") "YAGEO")
        (field (name "ALTIUM_UNNAMED_1") "0R")
        (field (name "CREATED BY") "YTL")
      )
      (libsource (lib "*") (part "RESISTOR_Dup1"))
    )
    (comp (ref "R2523")
      (value "*")
      (footprint "R0402")
      (description "НЁУГєсД¤µзЧи,2R2,+/-5%,R0402,1/16W.")
      (fields
        (field (name "PCB FOOTPRINT") "R0402")
        (field (name "TOLERANCE") "5%")
        (field (name "MANUFACTURER") "YAGEO")
        (field (name "ALTIUM_UNNAMED_1") "2.2R")
        (field (name "CREATED BY") "YTL")
      )
      (libsource (lib "*") (part "RESISTOR_Dup1"))
    )
    (comp (ref "R2524")
      (value "*")
      (footprint "R0402")
      (description "НЁУГєсД¤µзЧи,2R2,+/-5%,R0402,1/16W.")
      (fields
        (field (name "PCB FOOTPRINT") "R0402")
        (field (name "TOLERANCE") "5%")
        (field (name "MANUFACTURER") "YAGEO")
        (field (name "ALTIUM_UNNAMED_1") "2.2R")
        (field (name "CREATED BY") "YTL")
      )
      (libsource (lib "*") (part "RESISTOR_Dup1"))
    )
    (comp (ref "R2525")
      (value "*")
      (footprint "R0402")
      (description "НЁУГєсД¤µзЧи,0R,+/-5%,R0402,1/16W.")
      (fields
        (field (name "PCB FOOTPRINT") "R0402")
        (field (name "TOLERANCE") "5%")
        (field (name "MANUFACTURER") "YAGEO")
        (field (name "ALTIUM_UNNAMED_1") "0R")
        (field (name "CREATED BY") "YTL")
      )
      (libsource (lib "*") (part "RESISTOR_Dup1"))
    )
    (comp (ref "R2526")
      (value "*")
      (footprint "R0402")
      (description "НЁУГєсД¤µзЧи,0R,+/-5%,R0805,1/8W.")
      (fields
        (field (name "PCB FOOTPRINT") "R0805")
        (field (name "TOLERANCE") "5%")
        (field (name "MANUFACTURER") "YAGEO")
        (field (name "OPTION") "DNP")
        (field (name "ALTIUM_UNNAMED_1") "0R")
        (field (name "CREATED BY") "YTL")
      )
      (libsource (lib "*") (part "RESISTOR_Dup1"))
    )
    (comp (ref "R2527")
      (value "*")
      (footprint "R0402")
      (description "НЁУГєсД¤µзЧи,0R,+/-5%,R0402,1/16W.")
      (fields
        (field (name "PCB FOOTPRINT") "R0402")
        (field (name "TOLERANCE") "5%")
        (field (name "MANUFACTURER") "YAGEO")
        (field (name "ALTIUM_UNNAMED_1") "0R")
        (field (name "CREATED BY") "YTL")
      )
      (libsource (lib "*") (part "RESISTOR_Dup1"))
    )
    (comp (ref "R2528")
      (value "*")
      (footprint "R0402")
      (description "НЁУГєсД¤µзЧи,2R2,+/-5%,R0402,1/16W.")
      (fields
        (field (name "PCB FOOTPRINT") "R0402")
        (field (name "TOLERANCE") "5%")
        (field (name "MANUFACTURER") "YAGEO")
        (field (name "ALTIUM_UNNAMED_1") "2.2R")
        (field (name "CREATED BY") "YTL")
      )
      (libsource (lib "*") (part "RESISTOR_Dup1"))
    )
    (comp (ref "R2529")
      (value "*")
      (footprint "R0402")
      (description "НЁУГєсД¤µзЧи,10K,+/-5%,R0402,1/16W.")
      (fields
        (field (name "PCB FOOTPRINT") "R0402")
        (field (name "TOLERANCE") "5%")
        (field (name "MANUFACTURER") "YAGEO")
        (field (name "OPTION") "DNP")
        (field (name "ALTIUM_UNNAMED_1") "10K")
        (field (name "CREATED BY") "YTL")
      )
      (libsource (lib "*") (part "RESISTOR_Dup1"))
    )
    (comp (ref "R2530")
      (value "*")
      (footprint "R0402")
      (description "НЁУГєсД¤µзЧи,2R2,+/-5%,R0402,1/16W.")
      (fields
        (field (name "PCB FOOTPRINT") "R0402")
        (field (name "TOLERANCE") "5%")
        (field (name "MANUFACTURER") "YAGEO")
        (field (name "ALTIUM_UNNAMED_1") "2.2R")
        (field (name "CREATED BY") "YTL")
      )
      (libsource (lib "*") (part "RESISTOR_Dup1"))
    )
    (comp (ref "R2531")
      (value "*")
      (footprint "R0402")
      (description "НЁУГєсД¤µзЧи,0R,+/-5%,R0402,1/16W.")
      (fields
        (field (name "PCB FOOTPRINT") "R0402")
        (field (name "TOLERANCE") "5%")
        (field (name "MANUFACTURER") "YAGEO")
        (field (name "ALTIUM_UNNAMED_1") "0R")
        (field (name "CREATED BY") "YTL")
      )
      (libsource (lib "*") (part "RESISTOR_Dup1"))
    )
    (comp (ref "R2532")
      (value "*")
      (footprint "R0402")
      (description "НЁУГєсД¤µзЧи,4K7,+/-5%,R0402,1/16W.")
      (fields
        (field (name "PCB FOOTPRINT") "R0402")
        (field (name "TOLERANCE") "5%")
        (field (name "MANUFACTURER") "YAGEO")
        (field (name "ALTIUM_UNNAMED_1") "4.7K")
        (field (name "CREATED BY") "YTL")
      )
      (libsource (lib "*") (part "RESISTOR_Dup1"))
    )
    (comp (ref "R2533")
      (value "*")
      (footprint "R0402")
      (description "НЁУГєсД¤µзЧи,100K,+/-5%,R0201,1/20W.")
      (fields
        (field (name "PCB FOOTPRINT") "R0201")
        (field (name "TOLERANCE") "5%")
        (field (name "MANUFACTURER") "YAGEO")
        (field (name "ALTIUM_UNNAMED_1") "100K")
        (field (name "CREATED BY") "YTL")
      )
      (libsource (lib "*") (part "RESISTOR_Dup1"))
    )
    (comp (ref "R2534")
      (value "*")
      (footprint "R0402")
      (description "НЁУГєсД¤µзЧи,100K,+/-5%,R0201,1/20W.")
      (fields
        (field (name "PCB FOOTPRINT") "R0201")
        (field (name "TOLERANCE") "5%")
        (field (name "MANUFACTURER") "YAGEO")
        (field (name "ALTIUM_UNNAMED_1") "100K")
        (field (name "CREATED BY") "YTL")
      )
      (libsource (lib "*") (part "RESISTOR_Dup1"))
    )
    (comp (ref "R2535")
      (value "*")
      (footprint "R0402")
      (description "НЁУГєсД¤µзЧи,2M,+/-5%,R0201,1/20W.")
      (fields
        (field (name "PCB FOOTPRINT") "R0201")
        (field (name "TOLERANCE") "5%")
        (field (name "MANUFACTURER") "YAGEO")
        (field (name "ALTIUM_UNNAMED_1") "2M")
        (field (name "CREATED BY") "YTL")
      )
      (libsource (lib "*") (part "RESISTOR_Dup1"))
    )
    (comp (ref "R2536")
      (value "*")
      (footprint "R0402")
      (description "НЁУГєсД¤µзЧи,2M,+/-5%,R0201,1/20W.")
      (fields
        (field (name "PCB FOOTPRINT") "R0201")
        (field (name "TOLERANCE") "5%")
        (field (name "MANUFACTURER") "YAGEO")
        (field (name "ALTIUM_UNNAMED_1") "2M")
        (field (name "CREATED BY") "YTL")
      )
      (libsource (lib "*") (part "RESISTOR_Dup1"))
    )
    (comp (ref "R2537")
      (value "*")
      (footprint "R0402")
      (description "НЁУГєсД¤µзЧи,0R,+/-5%,R0201,1/20W.")
      (fields
        (field (name "PCB FOOTPRINT") "R0201")
        (field (name "TOLERANCE") "5%")
        (field (name "MANUFACTURER") "YAGEO")
        (field (name "ALTIUM_UNNAMED_1") "0R")
        (field (name "CREATED BY") "YTL")
      )
      (libsource (lib "*") (part "RESISTOR_Dup1"))
    )
    (comp (ref "R2538")
      (value "*")
      (footprint "R0402")
      (description "НЁУГєсД¤µзЧи,0R,+/-5%,R0201,1/20W.")
      (fields
        (field (name "PCB FOOTPRINT") "R0201")
        (field (name "TOLERANCE") "5%")
        (field (name "MANUFACTURER") "YAGEO")
        (field (name "ALTIUM_UNNAMED_1") "0R")
        (field (name "CREATED BY") "YTL")
      )
      (libsource (lib "*") (part "RESISTOR_Dup1"))
    )
    (comp (ref "R2539")
      (value "*")
      (footprint "R0402")
      (description "НЁУГєсД¤µзЧи,0R,+/-5%,R1206,1/4W.")
      (fields
        (field (name "PCB FOOTPRINT") "R1206")
        (field (name "TOLERANCE") "5%")
        (field (name "MANUFACTURER") "YAGEO")
        (field (name "ALTIUM_UNNAMED_1") "0R")
        (field (name "CREATED BY") "YTL")
      )
      (libsource (lib "*") (part "RESISTOR_Dup1"))
    )
    (comp (ref "U2500")
      (value "*")
      (footprint "SOT_23_5")
      (description "Low Loss Power Distribution Switch")
      (fields
        (field (name "PCB FOOTPRINT") "SOT_23_5")
        (field (name "MANUFACTURER") "SilergyЈЁОщБ¦ЅЬЈ©")
        (field (name "ALTIUM_UNNAMED_1") "SY6280AAC")
        (field (name "CREATED BY") "JJJ")
      )
      (libsource (lib "*") (part "SWITCH_SY6280"))
    )
    (comp (ref "U2501")
      (value "*")
      (footprint "SOT_23_5")
      (description "Low Loss Power Distribution Switch")
      (fields
        (field (name "PCB FOOTPRINT") "SOT_23_5")
        (field (name "MANUFACTURER") "SilergyЈЁОщБ¦ЅЬЈ©")
        (field (name "ALTIUM_UNNAMED_1") "SY6280AAC")
        (field (name "CREATED BY") "JJJ")
      )
      (libsource (lib "*") (part "SWITCH_SY6280"))
    )
    (comp (ref "U2502")
      (value "*")
      (footprint "SOT_23_5")
      (description "Low Loss Power Distribution Switch")
      (fields
        (field (name "PCB FOOTPRINT") "SOT_23_5")
        (field (name "MANUFACTURER") "SilergyЈЁОщБ¦ЅЬЈ©")
        (field (name "ALTIUM_UNNAMED_1") "SY6280AAC")
        (field (name "CREATED BY") "JJJ")
      )
      (libsource (lib "*") (part "SWITCH_SY6280"))
    )
    (comp (ref "U2503")
      (value "*")
      (footprint "MLP14_2R50X2R50X0R80")
      (description "Programmable USB Type-C Controller w/PD")
      (fields
        (field (name "PCB FOOTPRINT") "MLP14_2R50X2R50X0R80")
        (field (name "MANUFACTURER") "Fairchild(·ЙХЧ°лµјМе)")
        (field (name "ALTIUM_UNNAMED_1") "FUSB302BMPX")
        (field (name "CREATED BY") "JJJ")
      )
      (libsource (lib "*") (part "USB_FUSB302B"))
    )
  )
  (nets
    (net (code "1") (name "/TYPEC0_CC1") (class "Default")
      (node (ref "C2521") (pin "1") (pinfunction "1_1") (pintype "passive"))
      (node (ref "D2518") (pin "1") (pinfunction "1_1") (pintype "passive"))
      (node (ref "J2500") (pin "A5") (pinfunction "CC1_A5") (pintype "passive"))
      (node (ref "U2503") (pin "10") (pinfunction "CC1_10_10") (pintype "passive"))
      (node (ref "U2503") (pin "11") (pinfunction "CC1_11_11") (pintype "passive"))
    )
    (net (code "2") (name "/TYPEC0_CC2") (class "Default")
      (node (ref "C2520") (pin "1") (pinfunction "1_1") (pintype "passive"))
      (node (ref "D2519") (pin "1") (pinfunction "1_1") (pintype "passive"))
      (node (ref "J2500") (pin "B5") (pinfunction "CC2_B5") (pintype "passive"))
      (node (ref "U2503") (pin "1") (pinfunction "CC2_1_1") (pintype "passive"))
      (node (ref "U2503") (pin "14") (pinfunction "CC2_14_14") (pintype "passive"))
    )
    (net (code "3") (name "/TYPEC0_DM") (class "Default")
      (node (ref "D2505") (pin "1") (pinfunction "1_1") (pintype "passive"))
      (node (ref "J2500") (pin "A7") (pinfunction "D-1_A7") (pintype "passive"))
      (node (ref "J2500") (pin "B7") (pinfunction "D-2_B7") (pintype "passive"))
      (node (ref "L2500") (pin "1") (pinfunction "1_1") (pintype "passive"))
      (node (ref "R2509") (pin "2") (pinfunction "2_2") (pintype "passive"))
    )
    (net (code "4") (name "/TYPEC0_DP") (class "Default")
      (node (ref "D2504") (pin "1") (pinfunction "1_1") (pintype "passive"))
      (node (ref "J2500") (pin "A6") (pinfunction "D+1_A6") (pintype "passive"))
      (node (ref "J2500") (pin "B6") (pinfunction "D+2_B6") (pintype "passive"))
      (node (ref "L2500") (pin "3") (pinfunction "3_3") (pintype "passive"))
      (node (ref "R2506") (pin "2") (pinfunction "2_2") (pintype "passive"))
    )
    (net (code "5") (name "/TYPEC0_RX1N") (class "Default")
      (node (ref "ED2500") (pin "1") (pinfunction "IO1_1") (pintype "passive"))
      (node (ref "ED2500") (pin "10") (pinfunction "NC_10_10") (pintype "passive"))
      (node (ref "J2500") (pin "B10") (pinfunction "RX1-_B10") (pintype "passive"))
      (node (ref "R2502") (pin "2") (pinfunction "2_2") (pintype "passive"))
    )
    (net (code "6") (name "/TYPEC0_RX1P") (class "Default")
      (node (ref "ED2500") (pin "2") (pinfunction "IO2_2") (pintype "passive"))
      (node (ref "ED2500") (pin "9") (pinfunction "NC_9_9") (pintype "passive"))
      (node (ref "J2500") (pin "B11") (pinfunction "RX1+_B11") (pintype "passive"))
      (node (ref "R2503") (pin "2") (pinfunction "2_2") (pintype "passive"))
    )
    (net (code "7") (name "/TYPEC0_RX2N") (class "Default")
      (node (ref "ED2501") (pin "1") (pinfunction "IO1_1") (pintype "passive"))
      (node (ref "ED2501") (pin "10") (pinfunction "NC_10_10") (pintype "passive"))
      (node (ref "J2500") (pin "A10") (pinfunction "RX2-_A10") (pintype "passive"))
      (node (ref "R2537") (pin "2") (pinfunction "2_2") (pintype "passive"))
    )
    (net (code "8") (name "/TYPEC0_RX2P") (class "Default")
      (node (ref "ED2501") (pin "2") (pinfunction "IO2_2") (pintype "passive"))
      (node (ref "ED2501") (pin "9") (pinfunction "NC_9_9") (pintype "passive"))
      (node (ref "J2500") (pin "A11") (pinfunction "RX2+_A11") (pintype "passive"))
      (node (ref "R2538") (pin "2") (pinfunction "2_2") (pintype "passive"))
    )
    (net (code "9") (name "/TYPEC0_SBU1") (class "Default")
      (node (ref "C2522") (pin "2") (pinfunction "2_2") (pintype "passive"))
      (node (ref "D2517") (pin "1") (pinfunction "1_1") (pintype "passive"))
      (node (ref "J2500") (pin "A8") (pinfunction "SBU1_A8") (pintype "passive"))
      (node (ref "R2533") (pin "2") (pinfunction "2_2") (pintype "passive"))
      (node (ref "R2536") (pin "1") (pinfunction "1_1") (pintype "passive"))
    )
    (net (code "10") (name "/TYPEC0_SBU2") (class "Default")
      (node (ref "C2523") (pin "2") (pinfunction "2_2") (pintype "passive"))
      (node (ref "D2516") (pin "1") (pinfunction "1_1") (pintype "passive"))
      (node (ref "J2500") (pin "B8") (pinfunction "SBU2_B8") (pintype "passive"))
      (node (ref "R2534") (pin "2") (pinfunction "2_2") (pintype "passive"))
      (node (ref "R2535") (pin "1") (pinfunction "1_1") (pintype "passive"))
    )
    (net (code "11") (name "/TYPEC0_TX1N") (class "Default")
      (node (ref "C2501") (pin "2") (pinfunction "2_2") (pintype "passive"))
      (node (ref "ED2500") (pin "5") (pinfunction "IO4_5") (pintype "passive"))
      (node (ref "ED2500") (pin "6") (pinfunction "NC_6_6") (pintype "passive"))
      (node (ref "J2500") (pin "A3") (pinfunction "TX1-_A3") (pintype "passive"))
    )
    (net (code "12") (name "/TYPEC0_TX1P") (class "Default")
      (node (ref "C2502") (pin "2") (pinfunction "2_2") (pintype "passive"))
      (node (ref "ED2500") (pin "4") (pinfunction "IO3_4") (pintype "passive"))
      (node (ref "ED2500") (pin "7") (pinfunction "NC_7_7") (pintype "passive"))
      (node (ref "J2500") (pin "A2") (pinfunction "TX1+_A2") (pintype "passive"))
    )
    (net (code "13") (name "/TYPEC0_TX2N") (class "Default")
      (node (ref "C2524") (pin "2") (pinfunction "2_2") (pintype "passive"))
      (node (ref "ED2501") (pin "5") (pinfunction "IO4_5") (pintype "passive"))
      (node (ref "ED2501") (pin "6") (pinfunction "NC_6_6") (pintype "passive"))
      (node (ref "J2500") (pin "B3") (pinfunction "TX2-_B3") (pintype "passive"))
    )
    (net (code "14") (name "/TYPEC0_TX2P") (class "Default")
      (node (ref "C2525") (pin "2") (pinfunction "2_2") (pintype "passive"))
      (node (ref "ED2501") (pin "4") (pinfunction "IO3_4") (pintype "passive"))
      (node (ref "ED2501") (pin "7") (pinfunction "NC_7_7") (pintype "passive"))
      (node (ref "J2500") (pin "B2") (pinfunction "TX2+_B2") (pintype "passive"))
    )
    (net (code "15") (name "/TYPEC1_USB20_HOST_DM") (class "Default")
      (node (ref "D2512") (pin "1") (pinfunction "1_1") (pintype "passive"))
      (node (ref "J2502") (pin "2") (pinfunction "2_2") (pintype "passive"))
      (node (ref "L2502") (pin "3") (pinfunction "3_3") (pintype "passive"))
      (node (ref "R2525") (pin "2") (pinfunction "2_2") (pintype "passive"))
    )
    (net (code "16") (name "/TYPEC1_USB20_HOST_DP") (class "Default")
      (node (ref "D2513") (pin "1") (pinfunction "1_1") (pintype "passive"))
      (node (ref "J2502") (pin "3") (pinfunction "3_3") (pintype "passive"))
      (node (ref "L2502") (pin "1") (pinfunction "1_1") (pintype "passive"))
      (node (ref "R2522") (pin "2") (pinfunction "2_2") (pintype "passive"))
    )
    (net (code "17") (name "/USB20_HOST0DM") (class "Default")
      (node (ref "D2511") (pin "1") (pinfunction "1_1") (pintype "passive"))
      (node (ref "J2501") (pin "2") (pinfunction "D-_2") (pintype "passive"))
      (node (ref "L2501") (pin "3") (pinfunction "3_3") (pintype "passive"))
      (node (ref "R2521") (pin "2") (pinfunction "2_2") (pintype "passive"))
    )
    (net (code "18") (name "/USB20_HOST0DP") (class "Default")
      (node (ref "D2510") (pin "1") (pinfunction "1_1") (pintype "passive"))
      (node (ref "J2501") (pin "3") (pinfunction "D+_3") (pintype "passive"))
      (node (ref "L2501") (pin "1") (pinfunction "1_1") (pintype "passive"))
      (node (ref "R2518") (pin "2") (pinfunction "2_2") (pintype "passive"))
    )
    (net (code "19") (name "/USB20_HOST1DM") (class "Default")
      (node (ref "D2514") (pin "1") (pinfunction "1_1") (pintype "passive"))
      (node (ref "J2503") (pin "2") (pinfunction "2_2") (pintype "passive"))
      (node (ref "L2503") (pin "3") (pinfunction "3_3") (pintype "passive"))
      (node (ref "R2531") (pin "2") (pinfunction "2_2") (pintype "passive"))
    )
    (net (code "20") (name "/USB20_HOST1DP") (class "Default")
      (node (ref "D2515") (pin "1") (pinfunction "1_1") (pintype "passive"))
      (node (ref "J2503") (pin "3") (pinfunction "3_3") (pintype "passive"))
      (node (ref "L2503") (pin "1") (pinfunction "1_1") (pintype "passive"))
      (node (ref "R2527") (pin "2") (pinfunction "2_2") (pintype "passive"))
    )
    (net (code "21") (name "/USB30_HOST2_SSRXN") (class "Default")
      (node (ref "D2507") (pin "1") (pinfunction "1_1") (pintype "passive"))
      (node (ref "J2501") (pin "5") (pinfunction "RX-_5") (pintype "passive"))
      (node (ref "R2512") (pin "2") (pinfunction "2_2") (pintype "passive"))
    )
    (net (code "22") (name "/USB30_HOST2_SSRXP") (class "Default")
      (node (ref "D2506") (pin "1") (pinfunction "1_1") (pintype "passive"))
      (node (ref "J2501") (pin "6") (pinfunction "RX+_6") (pintype "passive"))
      (node (ref "R2514") (pin "2") (pinfunction "2_2") (pintype "passive"))
    )
    (net (code "23") (name "/USB30_HOST2_SSTXN") (class "Default")
      (node (ref "C2509") (pin "2") (pinfunction "2_2") (pintype "passive"))
      (node (ref "D2508") (pin "1") (pinfunction "1_1") (pintype "passive"))
      (node (ref "J2501") (pin "8") (pinfunction "TX-_8") (pintype "passive"))
    )
    (net (code "24") (name "/USB30_HOST2_SSTXP") (class "Default")
      (node (ref "C2510") (pin "2") (pinfunction "2_2") (pintype "passive"))
      (node (ref "D2509") (pin "1") (pinfunction "1_1") (pintype "passive"))
      (node (ref "J2501") (pin "9") (pinfunction "TX+_9") (pintype "passive"))
    )
    (net (code "25") (name "GND") (class "Default")
      (node (ref "C2503") (pin "2") (pinfunction "2_2") (pintype "passive"))
      (node (ref "C2504") (pin "2") (pinfunction "2_2") (pintype "passive"))
      (node (ref "C2505") (pin "2") (pinfunction "2_2") (pintype "passive"))
      (node (ref "C2506") (pin "2") (pinfunction "2_2") (pintype "passive"))
      (node (ref "C2507") (pin "2") (pinfunction "2_2") (pintype "passive"))
      (node (ref "C2508") (pin "2") (pinfunction "2_2") (pintype "passive"))
      (node (ref "C2511") (pin "2") (pinfunction "2_2") (pintype "passive"))
      (node (ref "C2512") (pin "2") (pinfunction "2_2") (pintype "passive"))
      (node (ref "C2513") (pin "2") (pinfunction "2_2") (pintype "passive"))
      (node (ref "C2515") (pin "2") (pinfunction "2_2") (pintype "passive"))
      (node (ref "C2516") (pin "2") (pinfunction "2_2") (pintype "passive"))
      (node (ref "C2517") (pin "2") (pinfunction "2_2") (pintype "passive"))
      (node (ref "C2518") (pin "2") (pinfunction "2_2") (pintype "passive"))
      (node (ref "C2519") (pin "2") (pinfunction "2_2") (pintype "passive"))
      (node (ref "C2520") (pin "2") (pinfunction "2_2") (pintype "passive"))
      (node (ref "C2521") (pin "2") (pinfunction "2_2") (pintype "passive"))
      (node (ref "C2526") (pin "2") (pinfunction "2_2") (pintype "passive"))
      (node (ref "C2528") (pin "2") (pinfunction "2_2") (pintype "passive"))
      (node (ref "D2504") (pin "2") (pinfunction "2_2") (pintype "passive"))
      (node (ref "D2505") (pin "2") (pinfunction "2_2") (pintype "passive"))
      (node (ref "D2506") (pin "2") (pinfunction "2_2") (pintype "passive"))
      (node (ref "D2507") (pin "2") (pinfunction "2_2") (pintype "passive"))
      (node (ref "D2508") (pin "2") (pinfunction "2_2") (pintype "passive"))
      (node (ref "D2509") (pin "2") (pinfunction "2_2") (pintype "passive"))
      (node (ref "D2510") (pin "2") (pinfunction "2_2") (pintype "passive"))
      (node (ref "D2511") (pin "2") (pinfunction "2_2") (pintype "passive"))
      (node (ref "D2512") (pin "2") (pinfunction "2_2") (pintype "passive"))
      (node (ref "D2513") (pin "2") (pinfunction "2_2") (pintype "passive"))
      (node (ref "D2514") (pin "2") (pinfunction "2_2") (pintype "passive"))
      (node (ref "D2515") (pin "2") (pinfunction "2_2") (pintype "passive"))
      (node (ref "D2516") (pin "2") (pinfunction "2_2") (pintype "passive"))
      (node (ref "D2517") (pin "2") (pinfunction "2_2") (pintype "passive"))
      (node (ref "D2518") (pin "2") (pinfunction "2_2") (pintype "passive"))
      (node (ref "D2519") (pin "2") (pinfunction "2_2") (pintype "passive"))
      (node (ref "ED2500") (pin "3") (pinfunction "GND_3") (pintype "power_in"))
      (node (ref "ED2500") (pin "8") (pinfunction "GND_8") (pintype "power_in"))
      (node (ref "ED2501") (pin "3") (pinfunction "GND_3") (pintype "power_in"))
      (node (ref "ED2501") (pin "8") (pinfunction "GND_8") (pintype "power_in"))
      (node (ref "J2500") (pin "A1") (pinfunction "GND_A1") (pintype "power_in"))
      (node (ref "J2500") (pin "A12") (pinfunction "GND_A12") (pintype "power_in"))
      (node (ref "J2500") (pin "B1") (pinfunction "GND_B1") (pintype "power_in"))
      (node (ref "J2500") (pin "B12") (pinfunction "GND_B12") (pintype "power_in"))
      (node (ref "J2500") (pin "H1") (pinfunction "HOLE_1_H1") (pintype "power_in"))
      (node (ref "J2500") (pin "H2") (pinfunction "HOLE_2_H2") (pintype "power_in"))
      (node (ref "J2500") (pin "H3") (pinfunction "HOLE_3_H3") (pintype "power_in"))
      (node (ref "J2500") (pin "H4") (pinfunction "HOLE_4_H4") (pintype "power_in"))
      (node (ref "J2501") (pin "10") (pinfunction "G1_10") (pintype "passive"))
      (node (ref "J2501") (pin "11") (pinfunction "G2_11") (pintype "passive"))
      (node (ref "J2501") (pin "12") (pinfunction "G3_12") (pintype "passive"))
      (node (ref "J2501") (pin "13") (pinfunction "G4_13") (pintype "passive"))
      (node (ref "J2501") (pin "4") (pinfunction "GND4_4") (pintype "power_in"))
      (node (ref "J2501") (pin "7") (pinfunction "GND_7") (pintype "power_in"))
      (node (ref "J2502") (pin "4") (pinfunction "4_4") (pintype "passive"))
      (node (ref "J2502") (pin "5") (pinfunction "5_5") (pintype "passive"))
      (node (ref "J2502") (pin "6") (pinfunction "6_6") (pintype "passive"))
      (node (ref "J2503") (pin "4") (pinfunction "4_4") (pintype "passive"))
      (node (ref "J2503") (pin "5") (pinfunction "5_5") (pintype "passive"))
      (node (ref "J2503") (pin "6") (pinfunction "6_6") (pintype "passive"))
      (node (ref "R2501") (pin "2") (pinfunction "2_2") (pintype "passive"))
      (node (ref "R2505") (pin "2") (pinfunction "2_2") (pintype "passive"))
      (node (ref "R2510") (pin "2") (pinfunction "2_2") (pintype "passive"))
      (node (ref "R2511") (pin "2") (pinfunction "2_2") (pintype "passive"))
      (node (ref "R2515") (pin "2") (pinfunction "2_2") (pintype "passive"))
      (node (ref "R2516") (pin "2") (pinfunction "2_2") (pintype "passive"))
      (node (ref "R2517") (pin "2") (pinfunction "2_2") (pintype "passive"))
      (node (ref "R2529") (pin "2") (pinfunction "2_2") (pintype "passive"))
      (node (ref "R2532") (pin "2") (pinfunction "2_2") (pintype "passive"))
      (node (ref "R2535") (pin "2") (pinfunction "2_2") (pintype "passive"))
      (node (ref "R2536") (pin "2") (pinfunction "2_2") (pintype "passive"))
      (node (ref "U2500") (pin "2") (pinfunction "GND_2") (pintype "passive"))
      (node (ref "U2501") (pin "2") (pinfunction "GND_2") (pintype "passive"))
      (node (ref "U2502") (pin "2") (pinfunction "GND_2") (pintype "passive"))
      (node (ref "U2503") (pin "15") (pinfunction "ePAD_15") (pintype "power_in"))
      (node (ref "U2503") (pin "8") (pinfunction "GND_8_8") (pintype "power_in"))
      (node (ref "U2503") (pin "9") (pinfunction "GND_9_9") (pintype "power_in"))
    )
    (net (code "26") (name "I2C6_SCL_M0") (class "Default")
      (node (ref "U2503") (pin "6") (pinfunction "SCL_6") (pintype "passive"))
    )
    (net (code "27") (name "I2C6_SDA_M0") (class "Default")
      (node (ref "U2503") (pin "7") (pinfunction "SDA_7") (pintype "passive"))
    )
    (net (code "28") (name "Net-(L2500-Pad2)") (class "Default")
      (node (ref "L2500") (pin "2") (pinfunction "2_2") (pintype "passive"))
      (node (ref "R2508") (pin "2") (pinfunction "2_2") (pintype "passive"))
      (node (ref "R2509") (pin "1") (pinfunction "1_1") (pintype "passive"))
    )
    (net (code "29") (name "Net-(L2500-Pad4)") (class "Default")
      (node (ref "L2500") (pin "4") (pinfunction "4_4") (pintype "passive"))
      (node (ref "R2506") (pin "1") (pinfunction "1_1") (pintype "passive"))
      (node (ref "R2507") (pin "2") (pinfunction "2_2") (pintype "passive"))
    )
    (net (code "30") (name "Net-(L2501-Pad2)") (class "Default")
      (node (ref "L2501") (pin "2") (pinfunction "2_2") (pintype "passive"))
      (node (ref "R2518") (pin "1") (pinfunction "1_1") (pintype "passive"))
      (node (ref "R2519") (pin "2") (pinfunction "2_2") (pintype "passive"))
    )
    (net (code "31") (name "Net-(L2501-Pad4)") (class "Default")
      (node (ref "L2501") (pin "4") (pinfunction "4_4") (pintype "passive"))
      (node (ref "R2520") (pin "2") (pinfunction "2_2") (pintype "passive"))
      (node (ref "R2521") (pin "1") (pinfunction "1_1") (pintype "passive"))
    )
    (net (code "32") (name "Net-(L2502-Pad2)") (class "Default")
      (node (ref "L2502") (pin "2") (pinfunction "2_2") (pintype "passive"))
      (node (ref "R2522") (pin "1") (pinfunction "1_1") (pintype "passive"))
      (node (ref "R2523") (pin "2") (pinfunction "2_2") (pintype "passive"))
    )
    (net (code "33") (name "Net-(L2502-Pad4)") (class "Default")
      (node (ref "L2502") (pin "4") (pinfunction "4_4") (pintype "passive"))
      (node (ref "R2524") (pin "2") (pinfunction "2_2") (pintype "passive"))
      (node (ref "R2525") (pin "1") (pinfunction "1_1") (pintype "passive"))
    )
    (net (code "34") (name "Net-(L2503-Pad2)") (class "Default")
      (node (ref "L2503") (pin "2") (pinfunction "2_2") (pintype "passive"))
      (node (ref "R2527") (pin "1") (pinfunction "1_1") (pintype "passive"))
      (node (ref "R2528") (pin "2") (pinfunction "2_2") (pintype "passive"))
    )
    (net (code "35") (name "Net-(L2503-Pad4)") (class "Default")
      (node (ref "L2503") (pin "4") (pinfunction "4_4") (pintype "passive"))
      (node (ref "R2530") (pin "2") (pinfunction "2_2") (pintype "passive"))
      (node (ref "R2531") (pin "1") (pinfunction "1_1") (pintype "passive"))
    )
    (net (code "36") (name "Net-(U2500-OCB)") (class "Default")
      (node (ref "R2511") (pin "1") (pinfunction "1_1") (pintype "passive"))
      (node (ref "U2500") (pin "3") (pinfunction "OCB_3") (pintype "passive"))
    )
    (net (code "37") (name "Net-(U2500-VOUT)") (class "Default")
      (node (ref "C2526") (pin "1") (pinfunction "1_1") (pintype "passive"))
      (node (ref "R2539") (pin "1") (pinfunction "1_1") (pintype "passive"))
      (node (ref "U2500") (pin "1") (pinfunction "VOUT_1") (pintype "passive"))
    )
    (net (code "38") (name "Net-(U2501-OCB)") (class "Default")
      (node (ref "R2517") (pin "1") (pinfunction "1_1") (pintype "passive"))
      (node (ref "U2501") (pin "3") (pinfunction "OCB_3") (pintype "passive"))
    )
    (net (code "39") (name "Net-(U2502-OCB)") (class "Default")
      (node (ref "R2532") (pin "1") (pinfunction "1_1") (pintype "passive"))
      (node (ref "U2502") (pin "3") (pinfunction "OCB_3") (pintype "passive"))
    )
    (net (code "40") (name "TYPEC0_SBU1_DC") (class "Default")
      (node (ref "R2533") (pin "1") (pinfunction "1_1") (pintype "passive"))
    )
    (net (code "41") (name "TYPEC0_SBU1{slash}DP0_AUXP") (class "Default")
      (node (ref "C2522") (pin "1") (pinfunction "1_1") (pintype "passive"))
    )
    (net (code "42") (name "TYPEC0_SBU2_DC") (class "Default")
      (node (ref "R2534") (pin "1") (pinfunction "1_1") (pintype "passive"))
    )
    (net (code "43") (name "TYPEC0_SBU2{slash}DP0_AUXN") (class "Default")
      (node (ref "C2523") (pin "1") (pinfunction "1_1") (pintype "passive"))
    )
    (net (code "44") (name "TYPEC0_SSRX1N") (class "Default")
      (node (ref "R2502") (pin "1") (pinfunction "1_1") (pintype "passive"))
    )
    (net (code "45") (name "TYPEC0_SSRX1P") (class "Default")
      (node (ref "R2503") (pin "1") (pinfunction "1_1") (pintype "passive"))
    )
    (net (code "46") (name "TYPEC0_SSRX2N") (class "Default")
      (node (ref "R2537") (pin "1") (pinfunction "1_1") (pintype "passive"))
    )
    (net (code "47") (name "TYPEC0_SSRX2P") (class "Default")
      (node (ref "R2538") (pin "1") (pinfunction "1_1") (pintype "passive"))
    )
    (net (code "48") (name "TYPEC0_SSTX1N") (class "Default")
      (node (ref "C2501") (pin "1") (pinfunction "1_1") (pintype "passive"))
    )
    (net (code "49") (name "TYPEC0_SSTX1P") (class "Default")
      (node (ref "C2502") (pin "1") (pinfunction "1_1") (pintype "passive"))
    )
    (net (code "50") (name "TYPEC0_SSTX2N") (class "Default")
      (node (ref "C2524") (pin "1") (pinfunction "1_1") (pintype "passive"))
    )
    (net (code "51") (name "TYPEC0_SSTX2P") (class "Default")
      (node (ref "C2525") (pin "1") (pinfunction "1_1") (pintype "passive"))
    )
    (net (code "52") (name "TYPEC0_USB20_OTG_DM") (class "Default")
      (node (ref "R2508") (pin "1") (pinfunction "1_1") (pintype "passive"))
    )
    (net (code "53") (name "TYPEC0_USB20_OTG_DP") (class "Default")
      (node (ref "R2507") (pin "1") (pinfunction "1_1") (pintype "passive"))
    )
    (net (code "54") (name "TYPEC0_USB20_VBUSDET") (class "Default")
      (node (ref "R2500") (pin "1") (pinfunction "1_1") (pintype "passive"))
      (node (ref "R2501") (pin "1") (pinfunction "1_1") (pintype "passive"))
    )
    (net (code "55") (name "TYPEC1_USB20_OTG_DM") (class "Default")
      (node (ref "R2524") (pin "1") (pinfunction "1_1") (pintype "passive"))
    )
    (net (code "56") (name "TYPEC1_USB20_OTG_DP") (class "Default")
      (node (ref "R2523") (pin "1") (pinfunction "1_1") (pintype "passive"))
    )
    (net (code "57") (name "USB20_HOST0_DM") (class "Default")
      (node (ref "R2520") (pin "1") (pinfunction "1_1") (pintype "passive"))
    )
    (net (code "58") (name "USB20_HOST0_DP") (class "Default")
      (node (ref "R2519") (pin "1") (pinfunction "1_1") (pintype "passive"))
    )
    (net (code "59") (name "USB20_HOST1_DM") (class "Default")
      (node (ref "R2530") (pin "1") (pinfunction "1_1") (pintype "passive"))
    )
    (net (code "60") (name "USB20_HOST1_DP") (class "Default")
      (node (ref "R2528") (pin "1") (pinfunction "1_1") (pintype "passive"))
    )
    (net (code "61") (name "USB30_2_SSRXN") (class "Default")
      (node (ref "R2512") (pin "1") (pinfunction "1_1") (pintype "passive"))
    )
    (net (code "62") (name "USB30_2_SSRXP") (class "Default")
      (node (ref "R2514") (pin "1") (pinfunction "1_1") (pintype "passive"))
    )
    (net (code "63") (name "USB30_2_SSTXN") (class "Default")
      (node (ref "C2509") (pin "1") (pinfunction "1_1") (pintype "passive"))
    )
    (net (code "64") (name "USB30_2_SSTXP") (class "Default")
      (node (ref "C2510") (pin "1") (pinfunction "1_1") (pintype "passive"))
    )
    (net (code "65") (name "USBCC_INT_L_GPIO1_A0") (class "Default")
      (node (ref "U2503") (pin "5") (pinfunction "INT#_5") (pintype "passive"))
    )
    (net (code "66") (name "USB_HOST_PWREN_H_GPIO4_B0") (class "Default")
      (node (ref "R2516") (pin "1") (pinfunction "1_1") (pintype "passive"))
      (node (ref "U2501") (pin "4") (pinfunction "EN_4") (pintype "passive"))
      (node (ref "U2502") (pin "4") (pinfunction "EN_4") (pintype "passive"))
    )
    (net (code "67") (name "USB_OTG_PWREN_H_GPIO4_A7") (class "Default")
      (node (ref "R2510") (pin "1") (pinfunction "1_1") (pintype "passive"))
      (node (ref "U2500") (pin "4") (pinfunction "EN_4") (pintype "passive"))
    )
    (net (code "68") (name "VBUS5V0_TYPEC0") (class "Default")
      (node (ref "C2504") (pin "1") (pinfunction "1_1") (pintype "passive"))
      (node (ref "C2505") (pin "1") (pinfunction "1_1") (pintype "passive"))
      (node (ref "C2516") (pin "1") (pinfunction "1_1") (pintype "passive"))
      (node (ref "C2528") (pin "1") (pinfunction "1_1") (pintype "passive"))
      (node (ref "J2500") (pin "A4") (pinfunction "VBUS_A4") (pintype "power_in"))
      (node (ref "J2500") (pin "A9") (pinfunction "VBUS_A9") (pintype "power_in"))
      (node (ref "J2500") (pin "B4") (pinfunction "VBUS_B4") (pintype "power_in"))
      (node (ref "J2500") (pin "B9") (pinfunction "VBUS_B9") (pintype "power_in"))
      (node (ref "R2505") (pin "1") (pinfunction "1_1") (pintype "passive"))
      (node (ref "R2539") (pin "2") (pinfunction "2_2") (pintype "passive"))
      (node (ref "U2503") (pin "2") (pinfunction "VBUS_2") (pintype "passive"))
    )
    (net (code "69") (name "VCC5V0_SYS") (class "Default")
      (node (ref "C2503") (pin "1") (pinfunction "1_1") (pintype "passive"))
      (node (ref "C2506") (pin "1") (pinfunction "1_1") (pintype "passive"))
      (node (ref "C2511") (pin "1") (pinfunction "1_1") (pintype "passive"))
      (node (ref "C2517") (pin "1") (pinfunction "1_1") (pintype "passive"))
      (node (ref "C2518") (pin "1") (pinfunction "1_1") (pintype "passive"))
      (node (ref "R2513") (pin "1") (pinfunction "1_1") (pintype "passive"))
      (node (ref "R2526") (pin "1") (pinfunction "1_1") (pintype "passive"))
      (node (ref "U2500") (pin "5") (pinfunction "IN_5") (pintype "passive"))
      (node (ref "U2501") (pin "5") (pinfunction "IN_5") (pintype "passive"))
      (node (ref "U2502") (pin "5") (pinfunction "IN_5") (pintype "passive"))
      (node (ref "U2503") (pin "12") (pinfunction "VCONN_12_12") (pintype "passive"))
      (node (ref "U2503") (pin "13") (pinfunction "VCONN_13_13") (pintype "passive"))
    )
    (net (code "70") (name "VCC5V0_USB20_HOST") (class "Default")
      (node (ref "C2512") (pin "1") (pinfunction "1_1") (pintype "passive"))
      (node (ref "C2513") (pin "1") (pinfunction "1_1") (pintype "passive"))
      (node (ref "C2515") (pin "1") (pinfunction "1_1") (pintype "passive"))
      (node (ref "J2502") (pin "1") (pinfunction "1_1") (pintype "passive"))
      (node (ref "J2503") (pin "1") (pinfunction "1_1") (pintype "passive"))
      (node (ref "R2526") (pin "2") (pinfunction "2_2") (pintype "passive"))
      (node (ref "R2529") (pin "1") (pinfunction "1_1") (pintype "passive"))
      (node (ref "U2502") (pin "1") (pinfunction "VOUT_1") (pintype "passive"))
    )
    (net (code "71") (name "VCC5V0_USB30_HOST2") (class "Default")
      (node (ref "C2507") (pin "1") (pinfunction "1_1") (pintype "passive"))
      (node (ref "C2508") (pin "1") (pinfunction "1_1") (pintype "passive"))
      (node (ref "J2501") (pin "1") (pinfunction "VBUS_1") (pintype "power_in"))
      (node (ref "R2513") (pin "2") (pinfunction "2_2") (pintype "passive"))
      (node (ref "R2515") (pin "1") (pinfunction "1_1") (pintype "passive"))
      (node (ref "U2501") (pin "1") (pinfunction "VOUT_1") (pintype "passive"))
    )
    (net (code "72") (name "VCC_3V3") (class "Default")
      (node (ref "C2519") (pin "1") (pinfunction "1_1") (pintype "passive"))
      (node (ref "R2500") (pin "2") (pinfunction "2_2") (pintype "passive"))
      (node (ref "U2503") (pin "3") (pinfunction "VDD_3_3") (pintype "power_in"))
      (node (ref "U2503") (pin "4") (pinfunction "VDD_4_4") (pintype "power_in"))
    )
  )
)
